# Mynd_TI_AMP.net
KiCad netlist of a schematic drawn in Altium Designer
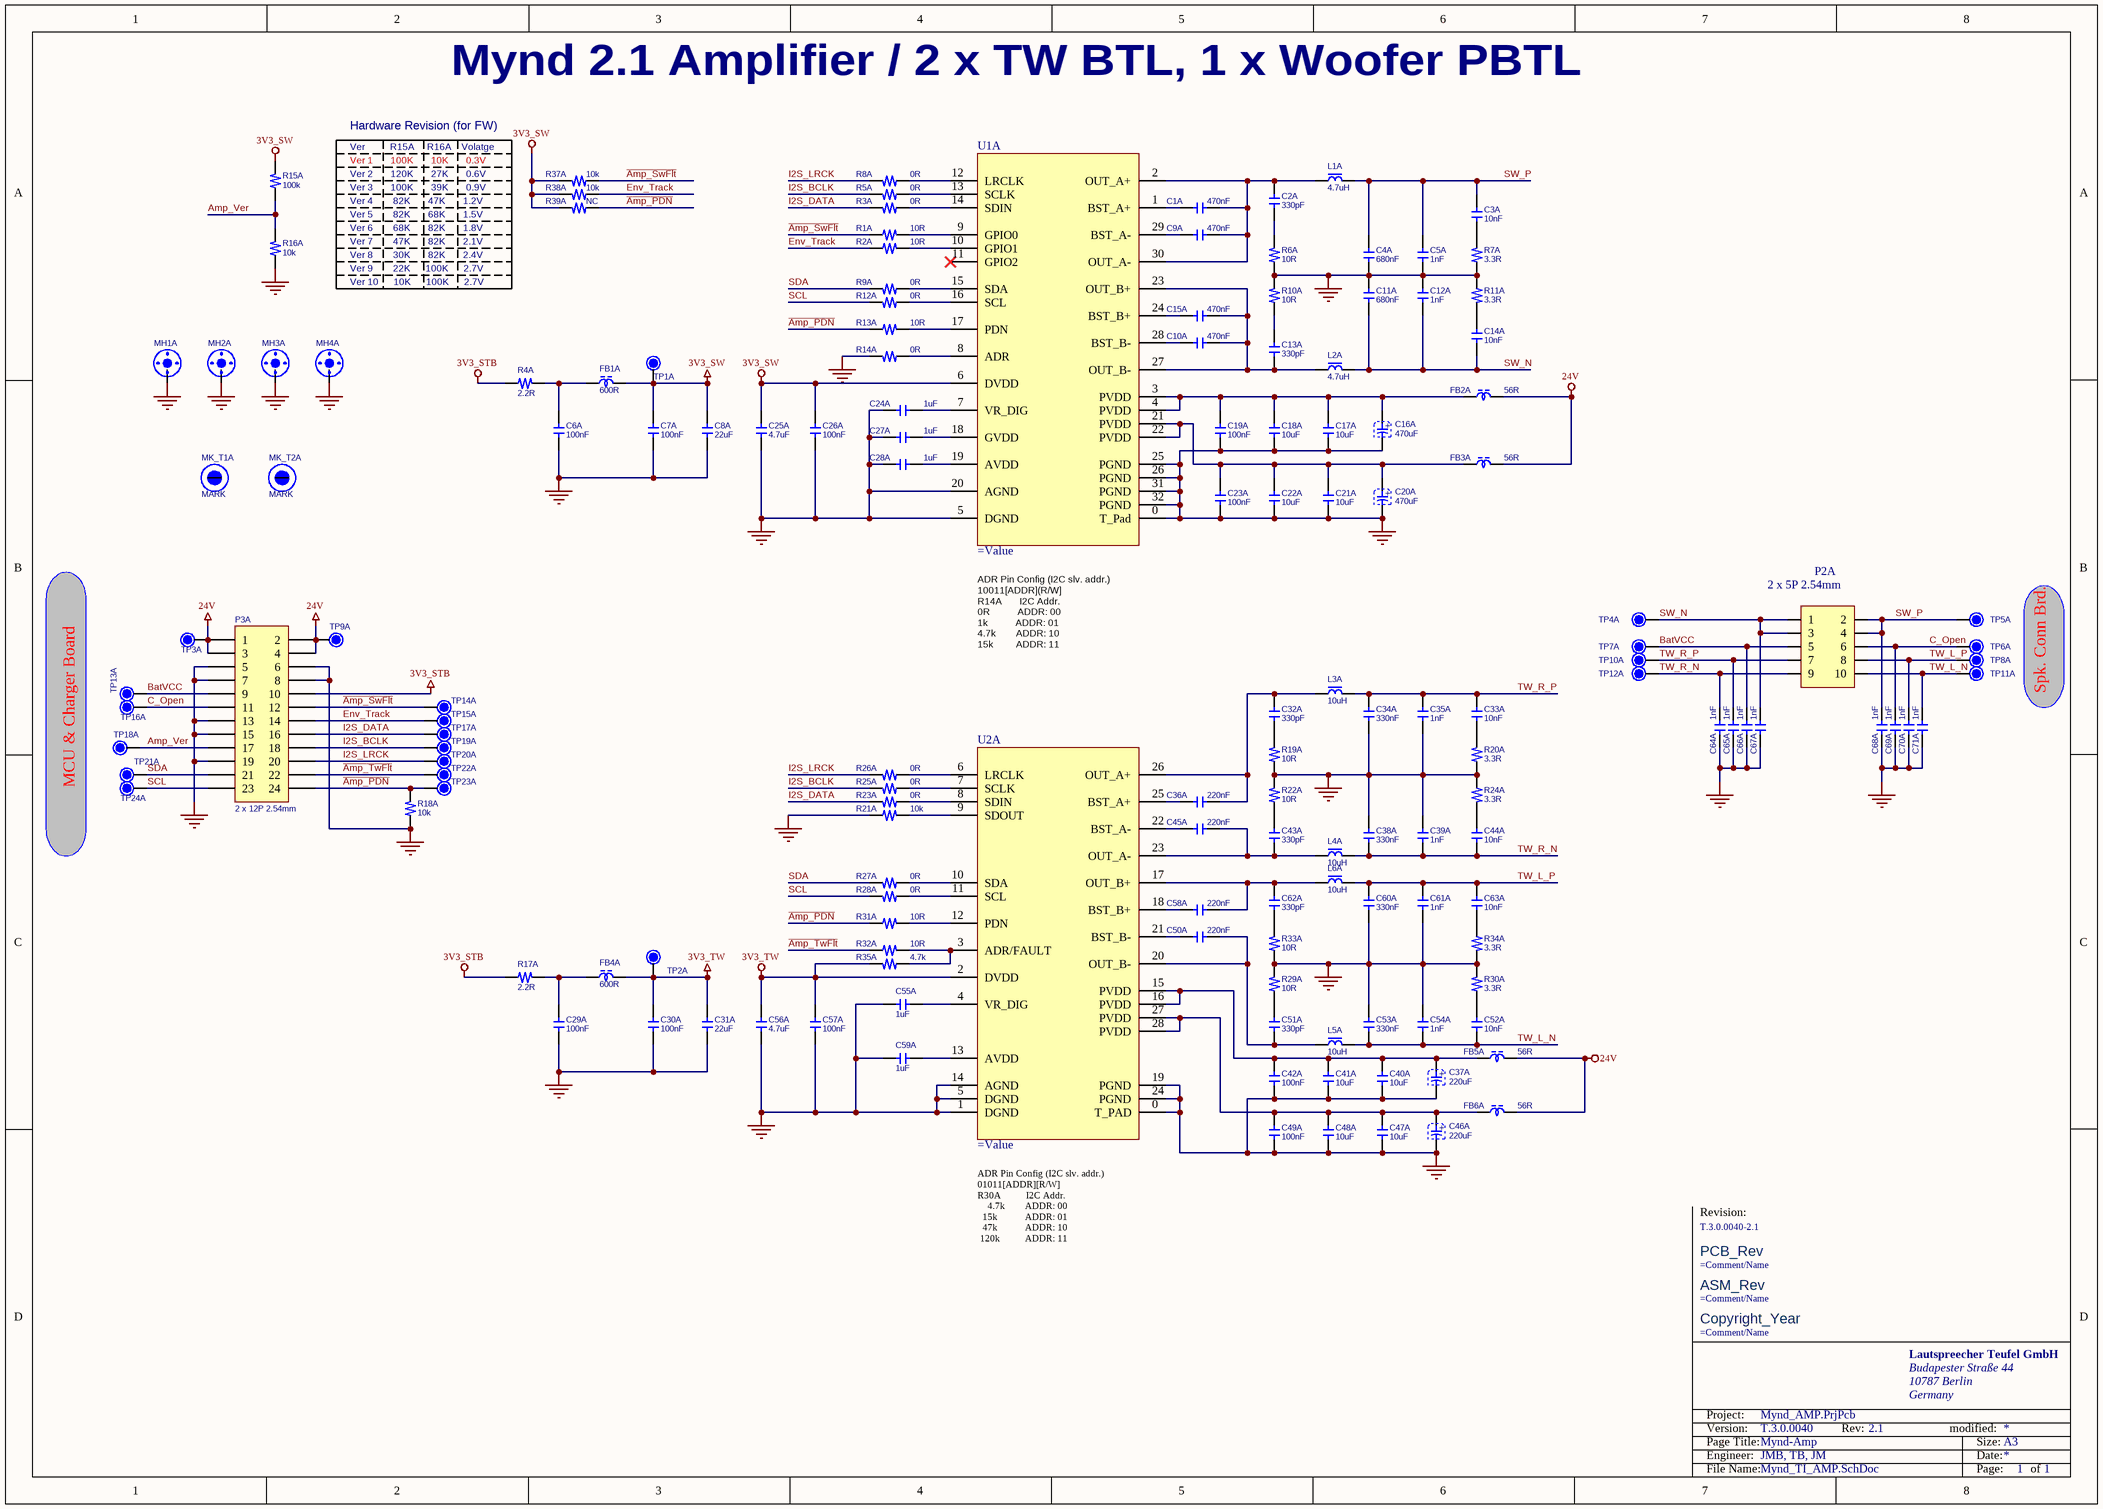
[diagram p0: Mynd_TI_AMP.SchDoc]

(export (version "E")
  (design (tool "Eeschema 10.0.6"))
  (components
    (comp (ref "C1A")
      (value "470nF")
      (footprint "C0603X100")
      (description "PSHF SMD M CAP 470nF 50V ±10% 0603 X7R")
      (fields (field (name "MANUFACTURER") "Multi-Sourced") (field (name "TOLERANCE") "±10%"))
      (libsource (lib "altium-import") (part "root_2_CAP1_"))
    )
    (comp (ref "C2A")
      (value "330pF")
      (footprint "C0603X80")
      (description "PSHF SMD M CAP 330pF 50V ±5% 0603 NPO")
      (fields (field (name "MANUFACTURER") "Multi-Sourced") (field (name "TOLERANCE") "±5%"))
      (libsource (lib "altium-import") (part "root_1_CAP1_"))
    )
    (comp (ref "C3A")
      (value "10nF")
      (footprint "C0603X100")
      (description "PSHF SMD M CAP 10nF 50V ±10% 0603 X7R")
      (fields (field (name "MANUFACTURER") "Multi-Sourced") (field (name "TOLERANCE") "±10%"))
      (libsource (lib "altium-import") (part "root_3_CAP1_"))
    )
    (comp (ref "C4A")
      (value "680nF")
      (footprint "C0805_125")
      (description "PSHF SMD M CAP 680nF 50V ±10% 0805 X7R")
      (fields (field (name "MANUFACTURER") "Multi-Sourced") (field (name "TOLERANCE") "±10%"))
      (libsource (lib "altium-import") (part "root_3_CAP1_"))
    )
    (comp (ref "C5A")
      (value "1nF")
      (footprint "C0805_125")
      (description "PSHF SMD M CAP 0.001uF 50V ±10% 0805 X7R")
      (fields (field (name "MANUFACTURER") "Multi-Sourced") (field (name "TOLERANCE") "±10%"))
      (libsource (lib "altium-import") (part "root_3_CAP1_"))
    )
    (comp (ref "C6A")
      (value "100nF")
      (footprint "C0603X105")
      (description "PSHF SMD M CAP 100nF 50V ±5% 0603 X7R")
      (fields (field (name "MANUFACTURER") "Multi-Sourced") (field (name "TOLERANCE") "±5%"))
      (libsource (lib "altium-import") (part "root_3_CAP1_"))
    )
    (comp (ref "C7A")
      (value "100nF")
      (footprint "C0603X105")
      (description "PSHF SMD M CAP 100nF 50V ±5% 0603 X7R")
      (fields (field (name "MANUFACTURER") "Multi-Sourced") (field (name "TOLERANCE") "±5%"))
      (libsource (lib "altium-import") (part "root_3_CAP1_"))
    )
    (comp (ref "C8A")
      (value "22uF")
      (footprint "C0805_145")
      (description "PSHF SMD M CAP 22uF 10V ±20% 0805 X5R")
      (fields (field (name "MANUFACTURER") "Multi-Sourced") (field (name "TOLERANCE") "±20%"))
      (libsource (lib "altium-import") (part "root_3_CAP1_"))
    )
    (comp (ref "C9A")
      (value "470nF")
      (footprint "C0603X100")
      (description "PSHF SMD M CAP 470nF 50V ±10% 0603 X7R")
      (fields (field (name "MANUFACTURER") "Multi-Sourced") (field (name "TOLERANCE") "±10%"))
      (libsource (lib "altium-import") (part "root_0_CAP1_"))
    )
    (comp (ref "C10A")
      (value "470nF")
      (footprint "C0603X100")
      (description "PSHF SMD M CAP 470nF 50V ±10% 0603 X7R")
      (fields (field (name "MANUFACTURER") "Multi-Sourced") (field (name "TOLERANCE") "±10%"))
      (libsource (lib "altium-import") (part "root_2_CAP1_"))
    )
    (comp (ref "C11A")
      (value "680nF")
      (footprint "C0805_125")
      (description "PSHF SMD M CAP 680nF 50V ±10% 0805 X7R")
      (fields (field (name "MANUFACTURER") "Multi-Sourced") (field (name "TOLERANCE") "±10%"))
      (libsource (lib "altium-import") (part "root_1_CAP1_"))
    )
    (comp (ref "C12A")
      (value "1nF")
      (footprint "C0805_125")
      (description "PSHF SMD M CAP 0.001uF 50V ±10% 0805 X7R")
      (fields (field (name "MANUFACTURER") "Multi-Sourced") (field (name "TOLERANCE") "±10%"))
      (libsource (lib "altium-import") (part "root_1_CAP1_"))
    )
    (comp (ref "C13A")
      (value "330pF")
      (footprint "C0603X80")
      (description "PSHF SMD M CAP 330pF 50V ±5% 0603 NPO")
      (fields (field (name "MANUFACTURER") "Multi-Sourced") (field (name "TOLERANCE") "±5%"))
      (libsource (lib "altium-import") (part "root_1_CAP1_"))
    )
    (comp (ref "C14A")
      (value "10nF")
      (footprint "C0603X100")
      (description "PSHF SMD M CAP 10nF 50V ±10% 0603 X7R")
      (fields (field (name "MANUFACTURER") "Multi-Sourced") (field (name "TOLERANCE") "±10%"))
      (libsource (lib "altium-import") (part "root_3_CAP1_"))
    )
    (comp (ref "C15A")
      (value "470nF")
      (footprint "C0603X100")
      (description "PSHF SMD M CAP 470nF 50V ±10% 0603 X7R")
      (fields (field (name "MANUFACTURER") "Multi-Sourced") (field (name "TOLERANCE") "±10%"))
      (libsource (lib "altium-import") (part "root_0_CAP1_"))
    )
    (comp (ref "C16A")
      (value "470uF")
      (footprint "ECAP_SMD_1000X1000")
      (description "PS SMD COND ELECT 470uF 35V ±20% 105℃")
      (fields (field (name "MANUFACTURER") "Multi-Sourced") (field (name "TOLERANCE") "±20%"))
      (libsource (lib "altium-import") (part "root_3_ECAP2_"))
    )
    (comp (ref "C17A")
      (value "10uF")
      (footprint "C1206")
      (description "PSHF SMD M CAP 10uF 50V ±10% 1206 X5R")
      (fields (field (name "MANUFACTURER") "Multi-Sourced") (field (name "TOLERANCE") "±10%"))
      (libsource (lib "altium-import") (part "root_3_CAP1_"))
    )
    (comp (ref "C18A")
      (value "10uF")
      (footprint "C1206")
      (description "PSHF SMD M CAP 10uF 50V ±10% 1206 X5R")
      (fields (field (name "MANUFACTURER") "Multi-Sourced") (field (name "TOLERANCE") "±10%"))
      (libsource (lib "altium-import") (part "root_3_CAP1_"))
    )
    (comp (ref "C19A")
      (value "100nF")
      (footprint "C0603X105")
      (description "PSHF SMD M CAP 100nF 50V ±5% 0603 X7R")
      (fields (field (name "MANUFACTURER") "Multi-Sourced") (field (name "TOLERANCE") "±5%"))
      (libsource (lib "altium-import") (part "root_3_CAP1_"))
    )
    (comp (ref "C20A")
      (value "470uF")
      (footprint "ECAP_SMD_1000X1000")
      (description "PS SMD COND ELECT 470uF 35V ±20% 105℃")
      (fields (field (name "MANUFACTURER") "Multi-Sourced") (field (name "TOLERANCE") "±20%"))
      (libsource (lib "altium-import") (part "root_3_ECAP2_"))
    )
    (comp (ref "C21A")
      (value "10uF")
      (footprint "C1206")
      (description "PSHF SMD M CAP 10uF 50V ±10% 1206 X5R")
      (fields (field (name "MANUFACTURER") "Multi-Sourced") (field (name "TOLERANCE") "±10%"))
      (libsource (lib "altium-import") (part "root_3_CAP1_"))
    )
    (comp (ref "C22A")
      (value "10uF")
      (footprint "C1206")
      (description "PSHF SMD M CAP 10uF 50V ±10% 1206 X5R")
      (fields (field (name "MANUFACTURER") "Multi-Sourced") (field (name "TOLERANCE") "±10%"))
      (libsource (lib "altium-import") (part "root_3_CAP1_"))
    )
    (comp (ref "C23A")
      (value "100nF")
      (footprint "C0603X105")
      (description "PSHF SMD M CAP 100nF 50V ±5% 0603 X7R")
      (fields (field (name "MANUFACTURER") "Multi-Sourced") (field (name "TOLERANCE") "±5%"))
      (libsource (lib "altium-import") (part "root_3_CAP1_"))
    )
    (comp (ref "C24A")
      (value "1uF")
      (footprint "C0603X105")
      (description "PSHF SMD M CAP 1uF 50V ±10% 0603 X7R")
      (fields (field (name "MANUFACTURER") "Multi-Sourced") (field (name "TOLERANCE") "±10%"))
      (libsource (lib "altium-import") (part "root_0_CAP1_"))
    )
    (comp (ref "C25A")
      (value "4.7uF")
      (footprint "C0805_145")
      (description "PSHF SMD M CAP 4.7uF 25V ±10% 0805 X7R")
      (fields (field (name "MANUFACTURER") "Multi-Sourced") (field (name "TOLERANCE") "±10%"))
      (libsource (lib "altium-import") (part "root_3_CAP1_"))
    )
    (comp (ref "C26A")
      (value "100nF")
      (footprint "C0603X105")
      (description "PSHF SMD M CAP 100nF 50V ±5% 0603 X7R")
      (fields (field (name "MANUFACTURER") "Multi-Sourced") (field (name "TOLERANCE") "±5%"))
      (libsource (lib "altium-import") (part "root_3_CAP1_"))
    )
    (comp (ref "C27A")
      (value "1uF")
      (footprint "C0603X105")
      (description "PSHF SMD M CAP 1uF 50V ±10% 0603 X7R")
      (fields (field (name "MANUFACTURER") "Multi-Sourced") (field (name "TOLERANCE") "±10%"))
      (libsource (lib "altium-import") (part "root_0_CAP1_"))
    )
    (comp (ref "C28A")
      (value "1uF")
      (footprint "C0603X105")
      (description "PSHF SMD M CAP 1uF 50V ±10% 0603 X7R")
      (fields (field (name "MANUFACTURER") "Multi-Sourced") (field (name "TOLERANCE") "±10%"))
      (libsource (lib "altium-import") (part "root_0_CAP1_"))
    )
    (comp (ref "C29A")
      (value "100nF")
      (footprint "C0603X105")
      (description "PSHF SMD M CAP 100nF 50V ±5% 0603 X7R")
      (fields (field (name "MANUFACTURER") "Multi-Sourced") (field (name "TOLERANCE") "±5%"))
      (libsource (lib "altium-import") (part "root_3_CAP1_"))
    )
    (comp (ref "C30A")
      (value "100nF")
      (footprint "C0603X105")
      (description "PSHF SMD M CAP 100nF 50V ±5% 0603 X7R")
      (fields (field (name "MANUFACTURER") "Multi-Sourced") (field (name "TOLERANCE") "±5%"))
      (libsource (lib "altium-import") (part "root_3_CAP1_"))
    )
    (comp (ref "C31A")
      (value "22uF")
      (footprint "C0805_145")
      (description "PSHF SMD M CAP 22uF 10V ±20% 0805 X5R")
      (fields (field (name "MANUFACTURER") "Multi-Sourced") (field (name "TOLERANCE") "±20%"))
      (libsource (lib "altium-import") (part "root_3_CAP1_"))
    )
    (comp (ref "C32A")
      (value "330pF")
      (footprint "C0603X80")
      (description "PSHF SMD M CAP 330pF 50V ±5% 0603 NPO")
      (fields (field (name "MANUFACTURER") "Multi-Sourced") (field (name "TOLERANCE") "±5%"))
      (libsource (lib "altium-import") (part "root_1_CAP1_"))
    )
    (comp (ref "C33A")
      (value "10nF")
      (footprint "C0603X100")
      (description "PSHF SMD M CAP 10nF 50V ±10% 0603 X7R")
      (fields (field (name "MANUFACTURER") "Multi-Sourced") (field (name "TOLERANCE") "±10%"))
      (libsource (lib "altium-import") (part "root_3_CAP1_"))
    )
    (comp (ref "C34A")
      (value "330nF")
      (footprint "C0805_125")
      (description "PSHF SMD M CAP 330nF 50V ±10% 0805 X7R")
      (fields (field (name "MANUFACTURER") "Multi-Sourced") (field (name "TOLERANCE") "±10%"))
      (libsource (lib "altium-import") (part "root_3_CAP1_"))
    )
    (comp (ref "C35A")
      (value "1nF")
      (footprint "C0805_125")
      (description "PSHF SMD M CAP 0.001uF 50V ±10% 0805 X7R")
      (fields (field (name "MANUFACTURER") "Multi-Sourced") (field (name "TOLERANCE") "±10%"))
      (libsource (lib "altium-import") (part "root_3_CAP1_"))
    )
    (comp (ref "C36A")
      (value "220nF")
      (footprint "C0603X100")
      (description "PSHF SMD M CAP 220nF 50V ±10% 0603 X7R")
      (fields (field (name "MANUFACTURER") "Multi-Sourced") (field (name "TOLERANCE") "±10%"))
      (libsource (lib "altium-import") (part "root_2_CAP1_"))
    )
    (comp (ref "C37A")
      (value "220uF")
      (footprint "ECAP_SMD_800X1000")
      (description "PS SMD COND ELECT 220uF 35V ±20% 105℃")
      (fields (field (name "MANUFACTURER") "[LELON]") (field (name "TOLERANCE") "±20%"))
      (libsource (lib "altium-import") (part "root_3_ECAP2_"))
    )
    (comp (ref "C38A")
      (value "330nF")
      (footprint "C0805_125")
      (description "PSHF SMD M CAP 330nF 50V ±10% 0805 X7R")
      (fields (field (name "MANUFACTURER") "Multi-Sourced") (field (name "TOLERANCE") "±10%"))
      (libsource (lib "altium-import") (part "root_1_CAP1_"))
    )
    (comp (ref "C39A")
      (value "1nF")
      (footprint "C0805_125")
      (description "PSHF SMD M CAP 0.001uF 50V ±10% 0805 X7R")
      (fields (field (name "MANUFACTURER") "Multi-Sourced") (field (name "TOLERANCE") "±10%"))
      (libsource (lib "altium-import") (part "root_1_CAP1_"))
    )
    (comp (ref "C40A")
      (value "10uF")
      (footprint "C1206")
      (description "PSHF SMD M CAP 10uF 50V ±10% 1206 X5R")
      (fields (field (name "MANUFACTURER") "Multi-Sourced") (field (name "TOLERANCE") "±10%"))
      (libsource (lib "altium-import") (part "root_3_CAP1_"))
    )
    (comp (ref "C41A")
      (value "10uF")
      (footprint "C1206")
      (description "PSHF SMD M CAP 10uF 50V ±10% 1206 X5R")
      (fields (field (name "MANUFACTURER") "Multi-Sourced") (field (name "TOLERANCE") "±10%"))
      (libsource (lib "altium-import") (part "root_3_CAP1_"))
    )
    (comp (ref "C42A")
      (value "100nF")
      (footprint "C0603X105")
      (description "PSHF SMD M CAP 100nF 50V ±5% 0603 X7R")
      (fields (field (name "MANUFACTURER") "Multi-Sourced") (field (name "TOLERANCE") "±5%"))
      (libsource (lib "altium-import") (part "root_3_CAP1_"))
    )
    (comp (ref "C43A")
      (value "330pF")
      (footprint "C0603X80")
      (description "PSHF SMD M CAP 330pF 50V ±5% 0603 NPO")
      (fields (field (name "MANUFACTURER") "Multi-Sourced") (field (name "TOLERANCE") "±5%"))
      (libsource (lib "altium-import") (part "root_1_CAP1_"))
    )
    (comp (ref "C44A")
      (value "10nF")
      (footprint "C0603X100")
      (description "PSHF SMD M CAP 10nF 50V ±10% 0603 X7R")
      (fields (field (name "MANUFACTURER") "Multi-Sourced") (field (name "TOLERANCE") "±10%"))
      (libsource (lib "altium-import") (part "root_3_CAP1_"))
    )
    (comp (ref "C45A")
      (value "220nF")
      (footprint "C0603X100")
      (description "PSHF SMD M CAP 220nF 50V ±10% 0603 X7R")
      (fields (field (name "MANUFACTURER") "Multi-Sourced") (field (name "TOLERANCE") "±10%"))
      (libsource (lib "altium-import") (part "root_0_CAP1_"))
    )
    (comp (ref "C46A")
      (value "220uF")
      (footprint "ECAP_SMD_800X1000")
      (description "PS SMD COND ELECT 220uF 35V ±20% 105℃")
      (fields (field (name "MANUFACTURER") "[LELON]") (field (name "TOLERANCE") "±20%"))
      (libsource (lib "altium-import") (part "root_3_ECAP2_"))
    )
    (comp (ref "C47A")
      (value "10uF")
      (footprint "C1206")
      (description "PSHF SMD M CAP 10uF 50V ±10% 1206 X5R")
      (fields (field (name "MANUFACTURER") "Multi-Sourced") (field (name "TOLERANCE") "±10%"))
      (libsource (lib "altium-import") (part "root_3_CAP1_"))
    )
    (comp (ref "C48A")
      (value "10uF")
      (footprint "C1206")
      (description "PSHF SMD M CAP 10uF 50V ±10% 1206 X5R")
      (fields (field (name "MANUFACTURER") "Multi-Sourced") (field (name "TOLERANCE") "±10%"))
      (libsource (lib "altium-import") (part "root_3_CAP1_"))
    )
    (comp (ref "C49A")
      (value "100nF")
      (footprint "C0603X105")
      (description "PSHF SMD M CAP 100nF 50V ±5% 0603 X7R")
      (fields (field (name "MANUFACTURER") "Multi-Sourced") (field (name "TOLERANCE") "±5%"))
      (libsource (lib "altium-import") (part "root_3_CAP1_"))
    )
    (comp (ref "C50A")
      (value "220nF")
      (footprint "C0603X100")
      (description "PSHF SMD M CAP 220nF 50V ±10% 0603 X7R")
      (fields (field (name "MANUFACTURER") "Multi-Sourced") (field (name "TOLERANCE") "±10%"))
      (libsource (lib "altium-import") (part "root_0_mirrored_CAP1_"))
    )
    (comp (ref "C51A")
      (value "330pF")
      (footprint "C0603X80")
      (description "PSHF SMD M CAP 330pF 50V ±5% 0603 NPO")
      (fields (field (name "MANUFACTURER") "Multi-Sourced") (field (name "TOLERANCE") "±5%"))
      (libsource (lib "altium-import") (part "root_3_mirrored_CAP1_"))
    )
    (comp (ref "C52A")
      (value "10nF")
      (footprint "C0603X100")
      (description "PSHF SMD M CAP 10nF 50V ±10% 0603 X7R")
      (fields (field (name "MANUFACTURER") "Multi-Sourced") (field (name "TOLERANCE") "±10%"))
      (libsource (lib "altium-import") (part "root_1_mirrored_CAP1_"))
    )
    (comp (ref "C53A")
      (value "330nF")
      (footprint "C0805_125")
      (description "PSHF SMD M CAP 330nF 50V ±10% 0805 X7R")
      (fields (field (name "MANUFACTURER") "Multi-Sourced") (field (name "TOLERANCE") "±10%"))
      (libsource (lib "altium-import") (part "root_1_mirrored_CAP1_"))
    )
    (comp (ref "C54A")
      (value "1nF")
      (footprint "C0805_125")
      (description "PSHF SMD M CAP 0.001uF 50V ±10% 0805 X7R")
      (fields (field (name "MANUFACTURER") "Multi-Sourced") (field (name "TOLERANCE") "±10%"))
      (libsource (lib "altium-import") (part "root_1_mirrored_CAP1_"))
    )
    (comp (ref "C55A")
      (value "1uF")
      (footprint "C0603X105")
      (description "PSHF SMD M CAP 1uF 50V ±10% 0603 X7R")
      (fields (field (name "MANUFACTURER") "Multi-Sourced") (field (name "TOLERANCE") "±10%"))
      (libsource (lib "altium-import") (part "root_0_CAP1_"))
    )
    (comp (ref "C56A")
      (value "4.7uF")
      (footprint "C0805_145")
      (description "PSHF SMD M CAP 4.7uF 25V ±10% 0805 X7R")
      (fields (field (name "MANUFACTURER") "Multi-Sourced") (field (name "TOLERANCE") "±10%"))
      (libsource (lib "altium-import") (part "root_3_CAP1_"))
    )
    (comp (ref "C57A")
      (value "100nF")
      (footprint "C0603X105")
      (description "PSHF SMD M CAP 100nF 50V ±5% 0603 X7R")
      (fields (field (name "MANUFACTURER") "Multi-Sourced") (field (name "TOLERANCE") "±5%"))
      (libsource (lib "altium-import") (part "root_3_CAP1_"))
    )
    (comp (ref "C58A")
      (value "220nF")
      (footprint "C0603X100")
      (description "PSHF SMD M CAP 220nF 50V ±10% 0603 X7R")
      (fields (field (name "MANUFACTURER") "Multi-Sourced") (field (name "TOLERANCE") "±10%"))
      (libsource (lib "altium-import") (part "root_2_mirrored_CAP1_"))
    )
    (comp (ref "C59A")
      (value "1uF")
      (footprint "C0603X105")
      (description "PSHF SMD M CAP 1uF 50V ±10% 0603 X7R")
      (fields (field (name "MANUFACTURER") "Multi-Sourced") (field (name "TOLERANCE") "±10%"))
      (libsource (lib "altium-import") (part "root_0_CAP1_"))
    )
    (comp (ref "C60A")
      (value "330nF")
      (footprint "C0805_125")
      (description "PSHF SMD M CAP 330nF 50V ±10% 0805 X7R")
      (fields (field (name "MANUFACTURER") "Multi-Sourced") (field (name "TOLERANCE") "±10%"))
      (libsource (lib "altium-import") (part "root_3_mirrored_CAP1_"))
    )
    (comp (ref "C61A")
      (value "1nF")
      (footprint "C0805_125")
      (description "PSHF SMD M CAP 0.001uF 50V ±10% 0805 X7R")
      (fields (field (name "MANUFACTURER") "Multi-Sourced") (field (name "TOLERANCE") "±10%"))
      (libsource (lib "altium-import") (part "root_3_mirrored_CAP1_"))
    )
    (comp (ref "C62A")
      (value "330pF")
      (footprint "C0603X80")
      (description "PSHF SMD M CAP 330pF 50V ±5% 0603 NPO")
      (fields (field (name "MANUFACTURER") "Multi-Sourced") (field (name "TOLERANCE") "±5%"))
      (libsource (lib "altium-import") (part "root_3_mirrored_CAP1_"))
    )
    (comp (ref "C63A")
      (value "10nF")
      (footprint "C0603X100")
      (description "PSHF SMD M CAP 10nF 50V ±10% 0603 X7R")
      (fields (field (name "MANUFACTURER") "Multi-Sourced") (field (name "TOLERANCE") "±10%"))
      (libsource (lib "altium-import") (part "root_1_mirrored_CAP1_"))
    )
    (comp (ref "C64A")
      (value "1nF")
      (footprint "C0805_125")
      (description "PSHF SMD M CAP 0.001uF 50V ±10% 0805 X7R")
      (fields (field (name "MANUFACTURER") "Multi-Sourced") (field (name "TOLERANCE") "±10%"))
      (libsource (lib "altium-import") (part "root_3_CAP1_"))
    )
    (comp (ref "C65A")
      (value "1nF")
      (footprint "C0805_125")
      (description "PSHF SMD M CAP 0.001uF 50V ±10% 0805 X7R")
      (fields (field (name "MANUFACTURER") "Multi-Sourced") (field (name "TOLERANCE") "±10%"))
      (libsource (lib "altium-import") (part "root_3_CAP1_"))
    )
    (comp (ref "C66A")
      (value "1nF")
      (footprint "C0805_125")
      (description "PSHF SMD M CAP 0.001uF 50V ±10% 0805 X7R")
      (fields (field (name "MANUFACTURER") "Multi-Sourced") (field (name "TOLERANCE") "±10%"))
      (libsource (lib "altium-import") (part "root_3_CAP1_"))
    )
    (comp (ref "C67A")
      (value "1nF")
      (footprint "C0805_125")
      (description "PSHF SMD M CAP 0.001uF 50V ±10% 0805 X7R")
      (fields (field (name "MANUFACTURER") "Multi-Sourced") (field (name "TOLERANCE") "±10%"))
      (libsource (lib "altium-import") (part "root_3_CAP1_"))
    )
    (comp (ref "C68A")
      (value "1nF")
      (footprint "C0805_125")
      (description "PSHF SMD M CAP 0.001uF 50V ±10% 0805 X7R")
      (fields (field (name "MANUFACTURER") "Multi-Sourced") (field (name "TOLERANCE") "±10%"))
      (libsource (lib "altium-import") (part "root_3_CAP1_"))
    )
    (comp (ref "C69A")
      (value "1nF")
      (footprint "C0805_125")
      (description "PSHF SMD M CAP 0.001uF 50V ±10% 0805 X7R")
      (fields (field (name "MANUFACTURER") "Multi-Sourced") (field (name "TOLERANCE") "±10%"))
      (libsource (lib "altium-import") (part "root_3_CAP1_"))
    )
    (comp (ref "C70A")
      (value "1nF")
      (footprint "C0805_125")
      (description "PSHF SMD M CAP 0.001uF 50V ±10% 0805 X7R")
      (fields (field (name "MANUFACTURER") "Multi-Sourced") (field (name "TOLERANCE") "±10%"))
      (libsource (lib "altium-import") (part "root_3_CAP1_"))
    )
    (comp (ref "C71A")
      (value "1nF")
      (footprint "C0805_125")
      (description "PSHF SMD M CAP 0.001uF 50V ±10% 0805 X7R")
      (fields (field (name "MANUFACTURER") "Multi-Sourced") (field (name "TOLERANCE") "±10%"))
      (libsource (lib "altium-import") (part "root_3_CAP1_"))
    )
    (comp (ref "FB1A")
      (value "600R")
      (footprint "L0603")
      (description "PSHF SMD FERRITE BEAD 600OHM 25% 0603")
      (fields (field (name "MANUFACTURER") "TSA") (field (name "TOLERANCE") "1:25%"))
      (libsource (lib "altium-import") (part "root_0_Bead1_"))
    )
    (comp (ref "FB2A")
      (value "56R")
      (footprint "L1612")
      (description "SMD FERRITE BEAD 56Ohm 25% 1612")
      (fields (field (name "MANUFACTURER") "TSA") (field (name "TOLERANCE") "1:25%"))
      (libsource (lib "altium-import") (part "root_0_mirrored_Bead1_"))
    )
    (comp (ref "FB3A")
      (value "56R")
      (footprint "L1612")
      (description "SMD FERRITE BEAD 56Ohm 25% 1612")
      (fields (field (name "MANUFACTURER") "TSA") (field (name "TOLERANCE") "1:25%"))
      (libsource (lib "altium-import") (part "root_0_mirrored_Bead1_"))
    )
    (comp (ref "FB4A")
      (value "600R")
      (footprint "L0603")
      (description "PSHF SMD FERRITE BEAD 600OHM 25% 0603")
      (fields (field (name "MANUFACTURER") "TSA") (field (name "TOLERANCE") "1:25%"))
      (libsource (lib "altium-import") (part "root_0_Bead1_"))
    )
    (comp (ref "FB5A")
      (value "56R")
      (footprint "L1612")
      (description "SMD FERRITE BEAD 56Ohm 25% 1612")
      (fields (field (name "MANUFACTURER") "TSA") (field (name "TOLERANCE") "1:25%"))
      (libsource (lib "altium-import") (part "root_0_mirrored_Bead1_"))
    )
    (comp (ref "FB6A")
      (value "56R")
      (footprint "L1612")
      (description "SMD FERRITE BEAD 56Ohm 25% 1612")
      (fields (field (name "MANUFACTURER") "TSA") (field (name "TOLERANCE") "1:25%"))
      (libsource (lib "altium-import") (part "root_0_Bead1_"))
    )
    (comp (ref "L1A")
      (value "4.7uH")
      (footprint "IND_SMD_YT_SQU_L78XW70XH50")
      (description "PS INDUCTOR 4.7uH 20% 6.5A 7.8x7x4.8")
      (fields (field (name "MANUFACTURER") "CHAMPIONS") (field (name "VOLTAGE") "1V"))
      (libsource (lib "altium-import") (part "root_0_INDUCTOR1_"))
    )
    (comp (ref "L2A")
      (value "4.7uH")
      (footprint "IND_SMD_YT_SQU_L78XW70XH50")
      (description "PS INDUCTOR 4.7uH 20% 6.5A 7.8x7x4.8")
      (fields (field (name "MANUFACTURER") "CHAMPIONS") (field (name "VOLTAGE") "1V"))
      (libsource (lib "altium-import") (part "root_0_INDUCTOR1_"))
    )
    (comp (ref "L3A")
      (value "10uH")
      (footprint "IND_SMD_YT_SQU_L78XW70XH30")
      (description "GP SMD INDUCTOR 10uH 1MHz 1V NORM")
      (fields (field (name "MANUFACTURER") "[CHAMPIONS]") (field (name "VOLTAGE") "1V"))
      (libsource (lib "altium-import") (part "root_0_INDUCTOR1_"))
    )
    (comp (ref "L4A")
      (value "10uH")
      (footprint "IND_SMD_YT_SQU_L78XW70XH30")
      (description "GP SMD INDUCTOR 10uH 1MHz 1V NORM")
      (fields (field (name "MANUFACTURER") "[CHAMPIONS]") (field (name "VOLTAGE") "1V"))
      (libsource (lib "altium-import") (part "root_0_INDUCTOR1_"))
    )
    (comp (ref "L5A")
      (value "10uH")
      (footprint "IND_SMD_YT_SQU_L78XW70XH30")
      (description "GP SMD INDUCTOR 10uH 1MHz 1V NORM")
      (fields (field (name "MANUFACTURER") "[CHAMPIONS]") (field (name "VOLTAGE") "1V"))
      (libsource (lib "altium-import") (part "root_0_INDUCTOR1_"))
    )
    (comp (ref "L6A")
      (value "10uH")
      (footprint "IND_SMD_YT_SQU_L78XW70XH30")
      (description "GP SMD INDUCTOR 10uH 1MHz 1V NORM")
      (fields (field (name "MANUFACTURER") "[CHAMPIONS]") (field (name "VOLTAGE") "1V"))
      (libsource (lib "altium-import") (part "root_0_INDUCTOR1_"))
    )
    (comp (ref "MH1A")
      (value "SCREW_HOLE_D32")
      (footprint "SCREW_D32")
      (description "SCREW_HOLE D3.2mm")
      (libsource (lib "altium-import") (part "root_1_SCREW_HOLE_"))
    )
    (comp (ref "MH2A")
      (value "SCREW_HOLE_D32")
      (footprint "SCREW_D32")
      (description "SCREW_HOLE D3.2mm")
      (libsource (lib "altium-import") (part "root_1_SCREW_HOLE_"))
    )
    (comp (ref "MH3A")
      (value "SCREW_HOLE_D32")
      (footprint "SCREW_D32")
      (description "SCREW_HOLE D3.2mm")
      (libsource (lib "altium-import") (part "root_1_SCREW_HOLE_"))
    )
    (comp (ref "MH4A")
      (value "SCREW_HOLE_D32")
      (footprint "SCREW_D32")
      (description "SCREW_HOLE D3.2mm")
      (libsource (lib "altium-import") (part "root_1_SCREW_HOLE_"))
    )
    (comp (ref "MK_T1A")
      (value "MARK")
      (footprint "MARK")
      (description "MARK DOT")
      (libsource (lib "altium-import") (part "root_0_MARK_"))
    )
    (comp (ref "MK_T2A")
      (value "MARK")
      (footprint "MARK")
      (description "MARK DOT")
      (libsource (lib "altium-import") (part "root_0_MARK_"))
    )
    (comp (ref "P2A")
      (value "2 x 5P 2.54mm")
      (footprint "female_2X5_254")
      (description "SMD BTB CONNECTOR 10P P2.54mm GOLD")
      (fields (field (name "MANUFACTURER") "MINGHENG"))
      (libsource (lib "altium-import") (part "root_0_CON 2X5P_"))
    )
    (comp (ref "P3A")
      (value "2 x 12P 2.54mm")
      (footprint "Pin_Header_SMD_2X12_254")
      (description "SMD BTB CONNECTOR 24P P2.54mm GOLD")
      (fields (field (name "MANUFACTURER") "MINGHENG"))
      (libsource (lib "altium-import") (part "root_0_CON 2x12P_"))
    )
    (comp (ref "R1A")
      (value "10R")
      (footprint "R0603")
      (description "PS SMD RES. 10OHM 1/10W 5% 0603")
      (fields (field (name "TOLERANCE") "1%") (field (name "MANUFACTURER") "Multi-Sourced"))
      (libsource (lib "altium-import") (part "root_2_RES1_"))
    )
    (comp (ref "R2A")
      (value "10R")
      (footprint "R0603")
      (description "PS SMD RES. 10OHM 1/10W 5% 0603")
      (fields (field (name "TOLERANCE") "1%") (field (name "MANUFACTURER") "Multi-Sourced"))
      (libsource (lib "altium-import") (part "root_2_RES1_"))
    )
    (comp (ref "R3A")
      (value "0R")
      (footprint "R0603")
      (description "PS SMD RES. 0OHM 1/10W 5% 0603")
      (fields (field (name "TOLERANCE") "1%") (field (name "MANUFACTURER") "Multi-Sourced"))
      (libsource (lib "altium-import") (part "root_0_RES1_"))
    )
    (comp (ref "R4A")
      (value "2.2R")
      (footprint "R0603")
      (description "PS SMD RES. 2.2OHM 1/10W 5% 0603")
      (fields (field (name "TOLERANCE") "1%") (field (name "MANUFACTURER") "Multi-Sourced"))
      (libsource (lib "altium-import") (part "root_2_RES1_"))
    )
    (comp (ref "R5A")
      (value "0R")
      (footprint "R0603")
      (description "PS SMD RES. 0OHM 1/10W 5% 0603")
      (fields (field (name "TOLERANCE") "1%") (field (name "MANUFACTURER") "Multi-Sourced"))
      (libsource (lib "altium-import") (part "root_0_RES1_"))
    )
    (comp (ref "R6A")
      (value "10R")
      (footprint "R1206")
      (description "PS SMD RES. 10OHM 1/4W 5% 1206")
      (fields (field (name "TOLERANCE") "1%") (field (name "MANUFACTURER") "Multi-Sourced"))
      (libsource (lib "altium-import") (part "root_3_RES1_"))
    )
    (comp (ref "R7A")
      (value "3.3R")
      (footprint "R0603")
      (description "PS SMD RES. 3.3OHM 1/10W 1% 0603")
      (fields (field (name "TOLERANCE") "1%") (field (name "MANUFACTURER") "Multi-Sourced"))
      (libsource (lib "altium-import") (part "root_3_RES1_"))
    )
    (comp (ref "R8A")
      (value "0R")
      (footprint "R0603")
      (description "PS SMD RES. 0OHM 1/10W 5% 0603")
      (fields (field (name "TOLERANCE") "1%") (field (name "MANUFACTURER") "Multi-Sourced"))
      (libsource (lib "altium-import") (part "root_0_RES1_"))
    )
    (comp (ref "R9A")
      (value "0R")
      (footprint "R0603")
      (description "PS SMD RES. 0OHM 1/10W 5% 0603")
      (fields (field (name "TOLERANCE") "1%") (field (name "MANUFACTURER") "Multi-Sourced"))
      (libsource (lib "altium-import") (part "root_0_RES1_"))
    )
    (comp (ref "R10A")
      (value "10R")
      (footprint "R1206")
      (description "PS SMD RES. 10OHM 1/4W 5% 1206")
      (fields (field (name "TOLERANCE") "1%") (field (name "MANUFACTURER") "Multi-Sourced"))
      (libsource (lib "altium-import") (part "root_3_RES1_"))
    )
    (comp (ref "R11A")
      (value "3.3R")
      (footprint "R0603")
      (description "PS SMD RES. 3.3OHM 1/10W 1% 0603")
      (fields (field (name "TOLERANCE") "1%") (field (name "MANUFACTURER") "Multi-Sourced"))
      (libsource (lib "altium-import") (part "root_1_RES1_"))
    )
    (comp (ref "R12A")
      (value "0R")
      (footprint "R0603")
      (description "PS SMD RES. 0OHM 1/10W 5% 0603")
      (fields (field (name "TOLERANCE") "1%") (field (name "MANUFACTURER") "Multi-Sourced"))
      (libsource (lib "altium-import") (part "root_0_RES1_"))
    )
    (comp (ref "R13A")
      (value "10R")
      (footprint "R0603")
      (description "PS SMD RES. 10OHM 1/10W 5% 0603")
      (fields (field (name "TOLERANCE") "1%") (field (name "MANUFACTURER") "Multi-Sourced"))
      (libsource (lib "altium-import") (part "root_2_RES1_"))
    )
    (comp (ref "R14A")
      (value "0R")
      (footprint "R0603")
      (description "PS SMD RES. 0OHM 1/10W 5% 0603")
      (fields (field (name "TOLERANCE") "1%") (field (name "MANUFACTURER") "Multi-Sourced"))
      (libsource (lib "altium-import") (part "root_0_RES1_"))
    )
    (comp (ref "R15A")
      (value "100k")
      (footprint "R0603")
      (description "PS SMD RES. 100KOHM 1/10W 1% 0603")
      (fields (field (name "TOLERANCE") "1%") (field (name "MANUFACTURER") "Multi-Sourced"))
      (libsource (lib "altium-import") (part "root_3_RES1_"))
    )
    (comp (ref "R16A")
      (value "10k")
      (footprint "R0603")
      (description "PS SMD RES. 10KOHM 1/10W 1% 0603")
      (fields (field (name "TOLERANCE") "1%") (field (name "MANUFACTURER") "Multi-Sourced"))
      (libsource (lib "altium-import") (part "root_3_RES1_"))
    )
    (comp (ref "R17A")
      (value "2.2R")
      (footprint "R0603")
      (description "PS SMD RES. 2.2OHM 1/10W 5% 0603")
      (fields (field (name "TOLERANCE") "1%") (field (name "MANUFACTURER") "Multi-Sourced"))
      (libsource (lib "altium-import") (part "root_2_RES1_"))
    )
    (comp (ref "R18A")
      (value "10k")
      (footprint "R0603")
      (description "PS SMD RES. 10KOHM 1/10W 1% 0603")
      (fields (field (name "TOLERANCE") "1%") (field (name "MANUFACTURER") "Multi-Sourced"))
      (libsource (lib "altium-import") (part "root_3_RES1_"))
    )
    (comp (ref "R19A")
      (value "10R")
      (footprint "R1206")
      (description "PS SMD RES. 10OHM 1/4W 5% 1206")
      (fields (field (name "TOLERANCE") "1%") (field (name "MANUFACTURER") "Multi-Sourced"))
      (libsource (lib "altium-import") (part "root_3_RES1_"))
    )
    (comp (ref "R20A")
      (value "3.3R")
      (footprint "R0603")
      (description "PS SMD RES. 3.3OHM 1/10W 1% 0603")
      (fields (field (name "TOLERANCE") "1%") (field (name "MANUFACTURER") "Multi-Sourced"))
      (libsource (lib "altium-import") (part "root_3_RES1_"))
    )
    (comp (ref "R21A")
      (value "10k")
      (footprint "R0603")
      (description "PS SMD RES. 10KOHM 1/10W 1% 0603")
      (fields (field (name "TOLERANCE") "1%") (field (name "MANUFACTURER") "Multi-Sourced"))
      (libsource (lib "altium-import") (part "root_2_RES1_"))
    )
    (comp (ref "R22A")
      (value "10R")
      (footprint "R1206")
      (description "PS SMD RES. 10OHM 1/4W 5% 1206")
      (fields (field (name "TOLERANCE") "1%") (field (name "MANUFACTURER") "Multi-Sourced"))
      (libsource (lib "altium-import") (part "root_3_RES1_"))
    )
    (comp (ref "R23A")
      (value "0R")
      (footprint "R0603")
      (description "PS SMD RES. 0OHM 1/10W 5% 0603")
      (fields (field (name "TOLERANCE") "1%") (field (name "MANUFACTURER") "Multi-Sourced"))
      (libsource (lib "altium-import") (part "root_0_RES1_"))
    )
    (comp (ref "R24A")
      (value "3.3R")
      (footprint "R0603")
      (description "PS SMD RES. 3.3OHM 1/10W 1% 0603")
      (fields (field (name "TOLERANCE") "1%") (field (name "MANUFACTURER") "Multi-Sourced"))
      (libsource (lib "altium-import") (part "root_1_RES1_"))
    )
    (comp (ref "R25A")
      (value "0R")
      (footprint "R0603")
      (description "PS SMD RES. 0OHM 1/10W 5% 0603")
      (fields (field (name "TOLERANCE") "1%") (field (name "MANUFACTURER") "Multi-Sourced"))
      (libsource (lib "altium-import") (part "root_0_RES1_"))
    )
    (comp (ref "R26A")
      (value "0R")
      (footprint "R0603")
      (description "PS SMD RES. 0OHM 1/10W 5% 0603")
      (fields (field (name "TOLERANCE") "1%") (field (name "MANUFACTURER") "Multi-Sourced"))
      (libsource (lib "altium-import") (part "root_0_RES1_"))
    )
    (comp (ref "R27A")
      (value "0R")
      (footprint "R0603")
      (description "PS SMD RES. 0OHM 1/10W 5% 0603")
      (fields (field (name "TOLERANCE") "1%") (field (name "MANUFACTURER") "Multi-Sourced"))
      (libsource (lib "altium-import") (part "root_0_RES1_"))
    )
    (comp (ref "R28A")
      (value "0R")
      (footprint "R0603")
      (description "PS SMD RES. 0OHM 1/10W 5% 0603")
      (fields (field (name "TOLERANCE") "1%") (field (name "MANUFACTURER") "Multi-Sourced"))
      (libsource (lib "altium-import") (part "root_0_RES1_"))
    )
    (comp (ref "R29A")
      (value "10R")
      (footprint "R1206")
      (description "PS SMD RES. 10OHM 1/4W 5% 1206")
      (fields (field (name "TOLERANCE") "1%") (field (name "MANUFACTURER") "Multi-Sourced"))
      (libsource (lib "altium-import") (part "root_1_mirrored_RES1_"))
    )
    (comp (ref "R30A")
      (value "3.3R")
      (footprint "R0603")
      (description "PS SMD RES. 3.3OHM 1/10W 1% 0603")
      (fields (field (name "TOLERANCE") "1%") (field (name "MANUFACTURER") "Multi-Sourced"))
      (libsource (lib "altium-import") (part "root_1_mirrored_RES1_"))
    )
    (comp (ref "R31A")
      (value "10R")
      (footprint "R0603")
      (description "PS SMD RES. 10OHM 1/10W 5% 0603")
      (fields (field (name "TOLERANCE") "1%") (field (name "MANUFACTURER") "Multi-Sourced"))
      (libsource (lib "altium-import") (part "root_2_RES1_"))
    )
    (comp (ref "R32A")
      (value "10R")
      (footprint "R0603")
      (description "PS SMD RES. 10OHM 1/10W 5% 0603")
      (fields (field (name "TOLERANCE") "1%") (field (name "MANUFACTURER") "Multi-Sourced"))
      (libsource (lib "altium-import") (part "root_2_RES1_"))
    )
    (comp (ref "R33A")
      (value "10R")
      (footprint "R1206")
      (description "PS SMD RES. 10OHM 1/4W 5% 1206")
      (fields (field (name "TOLERANCE") "1%") (field (name "MANUFACTURER") "Multi-Sourced"))
      (libsource (lib "altium-import") (part "root_1_mirrored_RES1_"))
    )
    (comp (ref "R34A")
      (value "3.3R")
      (footprint "R0603")
      (description "PS SMD RES. 3.3OHM 1/10W 1% 0603")
      (fields (field (name "TOLERANCE") "1%") (field (name "MANUFACTURER") "Multi-Sourced"))
      (libsource (lib "altium-import") (part "root_3_mirrored_RES1_"))
    )
    (comp (ref "R35A")
      (value "4.7k")
      (footprint "R0603")
      (description "PS SMD RES. 4.7KOHM 1/10W 1% 0603")
      (fields (field (name "TOLERANCE") "1%") (field (name "MANUFACTURER") "Multi-Sourced"))
      (libsource (lib "altium-import") (part "root_0_RES1_"))
    )
    (comp (ref "R37A")
      (value "10k")
      (footprint "R0603")
      (description "PS SMD RES. 10KOHM 1/10W 1% 0603")
      (fields (field (name "TOLERANCE") "1%") (field (name "MANUFACTURER") "Multi-Sourced"))
      (libsource (lib "altium-import") (part "root_0_RES1_"))
    )
    (comp (ref "R38A")
      (value "10k")
      (footprint "R0603")
      (description "PS SMD RES. 10KOHM 1/10W 1% 0603")
      (fields (field (name "TOLERANCE") "1%") (field (name "MANUFACTURER") "Multi-Sourced"))
      (libsource (lib "altium-import") (part "root_0_RES1_"))
    )
    (comp (ref "R39A")
      (value "NC")
      (footprint "R0603")
      (description "PS SMD RES. 10KOHM 1/10W 1% 0603")
      (fields (field (name "TOLERANCE") "1%") (field (name "MANUFACTURER") "Multi-Sourced"))
      (libsource (lib "altium-import") (part "root_0_RES1_"))
    )
    (comp (ref "Teufel_ASM_Label1A")
      (value "~")
      (footprint "Teufel_ASM_Rev")
      (description "Teufel_ASM_Rev")
      (libsource (lib "altium-import") (part "root_0_Teufel_ASM_Label_"))
    )
    (comp (ref "Teufel_Copyright1A")
      (value "~")
      (footprint "TEUFEL_COPYRIGHT")
      (description "Teufel_Copyright_Year")
      (libsource (lib "altium-import") (part "root_0_Teufel_Copyright_"))
    )
    (comp (ref "Teufel_PCB_Label1A")
      (value "~")
      (footprint "Teufel_PCB_Rev")
      (description "Teufel_PCB_Label")
      (libsource (lib "altium-import") (part "root_0_Teufel_PCB_Label_"))
    )
    (comp (ref "Teufel_PCB_Logo1A")
      (value "-2.1")
      (footprint "Teufel_NoLogo")
      (description "Teufel PCB NoLogo")
      (libsource (lib "altium-import") (part "root_0_Teufel NoLogo_"))
    )
    (comp (ref "TP1A")
      (value "TP_T_60_40")
      (footprint "TP_T_60_40")
      (description "Test Point")
      (libsource (lib "altium-import") (part "root_1_TP_"))
    )
    (comp (ref "TP2A")
      (value "TP_T_60_40")
      (footprint "TP_T_60_40")
      (description "Test Point")
      (libsource (lib "altium-import") (part "root_1_TP_"))
    )
    (comp (ref "TP3A")
      (value "TP12")
      (footprint "TP120")
      (description "Test Point")
      (libsource (lib "altium-import") (part "root_2_TP_"))
    )
    (comp (ref "TP4A")
      (value "TP12")
      (footprint "TP120")
      (description "Test Point")
      (libsource (lib "altium-import") (part "root_2_TP_"))
    )
    (comp (ref "TP5A")
      (value "TP12")
      (footprint "TP120")
      (description "Test Point")
      (libsource (lib "altium-import") (part "root_0_TP_"))
    )
    (comp (ref "TP6A")
      (value "TP12")
      (footprint "TP120")
      (description "Test Point")
      (libsource (lib "altium-import") (part "root_0_TP_"))
    )
    (comp (ref "TP7A")
      (value "TP12")
      (footprint "TP120")
      (description "Test Point")
      (libsource (lib "altium-import") (part "root_2_TP_"))
    )
    (comp (ref "TP8A")
      (value "TP12")
      (footprint "TP120")
      (description "Test Point")
      (libsource (lib "altium-import") (part "root_0_TP_"))
    )
    (comp (ref "TP9A")
      (value "TP12")
      (footprint "TP120")
      (description "Test Point")
      (libsource (lib "altium-import") (part "root_0_TP_"))
    )
    (comp (ref "TP10A")
      (value "TP12")
      (footprint "TP120")
      (description "Test Point")
      (libsource (lib "altium-import") (part "root_2_TP_"))
    )
    (comp (ref "TP11A")
      (value "TP12")
      (footprint "TP120")
      (description "Test Point")
      (libsource (lib "altium-import") (part "root_0_TP_"))
    )
    (comp (ref "TP12A")
      (value "TP12")
      (footprint "TP120")
      (description "Test Point")
      (libsource (lib "altium-import") (part "root_2_TP_"))
    )
    (comp (ref "TP13A")
      (value "TP12")
      (footprint "TP120")
      (description "Test Point")
      (libsource (lib "altium-import") (part "root_2_TP_"))
    )
    (comp (ref "TP14A")
      (value "TP12")
      (footprint "TP120")
      (description "Test Point")
      (libsource (lib "altium-import") (part "root_0_TP_"))
    )
    (comp (ref "TP15A")
      (value "TP12")
      (footprint "TP120")
      (description "Test Point")
      (libsource (lib "altium-import") (part "root_0_TP_"))
    )
    (comp (ref "TP16A")
      (value "TP12")
      (footprint "TP120")
      (description "Test Point")
      (libsource (lib "altium-import") (part "root_2_TP_"))
    )
    (comp (ref "TP17A")
      (value "TP12")
      (footprint "TP120")
      (description "Test Point")
      (libsource (lib "altium-import") (part "root_0_TP_"))
    )
    (comp (ref "TP18A")
      (value "TP12")
      (footprint "TP120")
      (description "Test Point")
      (libsource (lib "altium-import") (part "root_2_TP_"))
    )
    (comp (ref "TP19A")
      (value "TP12")
      (footprint "TP120")
      (description "Test Point")
      (libsource (lib "altium-import") (part "root_0_TP_"))
    )
    (comp (ref "TP20A")
      (value "TP12")
      (footprint "TP120")
      (description "Test Point")
      (libsource (lib "altium-import") (part "root_0_TP_"))
    )
    (comp (ref "TP21A")
      (value "TP12")
      (footprint "TP120")
      (description "Test Point")
      (libsource (lib "altium-import") (part "root_2_TP_"))
    )
    (comp (ref "TP22A")
      (value "TP12")
      (footprint "TP120")
      (description "Test Point")
      (libsource (lib "altium-import") (part "root_0_TP_"))
    )
    (comp (ref "TP23A")
      (value "TP12")
      (footprint "TP120")
      (description "Test Point")
      (libsource (lib "altium-import") (part "root_0_TP_"))
    )
    (comp (ref "TP24A")
      (value "TP12")
      (footprint "TP120")
      (description "Test Point")
      (libsource (lib "altium-import") (part "root_2_TP_"))
    )
    (comp (ref "U1A")
      (value "~")
      (footprint "QFN32_500X500X100_50_P350X350")
      (description "GP SMD IC 32P VQFN TAS5825PRHBR TI")
      (fields (field (name "MANUFACTURER") "[TI]") (field (name "PART_NUMBER") "TAS5825PRHBR"))
      (libsource (lib "altium-import") (part "root_0_TAS5825P_"))
    )
    (comp (ref "U2A")
      (value "~")
      (footprint "TSSOP28(PWP)")
      (description "GP SMD IC 28P HTSSOP TAS5805MPWPR TI")
      (fields (field (name "MANUFACTURER") "[TI]") (field (name "PART_NUMBER") "TAS5805MPWPR"))
      (libsource (lib "altium-import") (part "root_0_TAS5805M_"))
    )
  )
  (nets
    (net (code "1") (name "/Amp_Ver") (class "Default")
      (node (ref "P3A") (pin "17") (pinfunction "17_17") (pintype "passive"))
      (node (ref "R15A") (pin "2") (pinfunction "2_2") (pintype "passive"))
      (node (ref "R16A") (pin "1") (pinfunction "1_1") (pintype "passive"))
      (node (ref "TP18A") (pin "1") (pinfunction "1_1") (pintype "passive"))
    )
    (net (code "2") (name "/BatVCC") (class "Default")
      (node (ref "C66A") (pin "1") (pinfunction "1_1") (pintype "passive"))
      (node (ref "P2A") (pin "5") (pinfunction "5_5") (pintype "passive"))
      (node (ref "P3A") (pin "9") (pinfunction "9_9") (pintype "passive"))
      (node (ref "TP13A") (pin "1") (pinfunction "1_1") (pintype "passive"))
      (node (ref "TP7A") (pin "1") (pinfunction "1_1") (pintype "passive"))
    )
    (net (code "3") (name "/C_Open") (class "Default")
      (node (ref "C69A") (pin "1") (pinfunction "1_1") (pintype "passive"))
      (node (ref "P2A") (pin "6") (pinfunction "6_6") (pintype "passive"))
      (node (ref "P3A") (pin "11") (pinfunction "11_11") (pintype "passive"))
      (node (ref "TP16A") (pin "1") (pinfunction "1_1") (pintype "passive"))
      (node (ref "TP6A") (pin "1") (pinfunction "1_1") (pintype "passive"))
    )
    (net (code "4") (name "/Env_Track") (class "Default")
      (node (ref "P3A") (pin "14") (pinfunction "14_14") (pintype "passive"))
      (node (ref "R2A") (pin "2") (pinfunction "2_2") (pintype "passive"))
      (node (ref "R38A") (pin "2") (pinfunction "2_2") (pintype "passive"))
      (node (ref "TP15A") (pin "1") (pinfunction "1_1") (pintype "passive"))
    )
    (net (code "5") (name "/I2S_BCLK") (class "Default")
      (node (ref "P3A") (pin "18") (pinfunction "18_18") (pintype "passive"))
      (node (ref "R25A") (pin "1") (pinfunction "1_1") (pintype "passive"))
      (node (ref "R5A") (pin "1") (pinfunction "1_1") (pintype "passive"))
      (node (ref "TP19A") (pin "1") (pinfunction "1_1") (pintype "passive"))
    )
    (net (code "6") (name "/I2S_DATA") (class "Default")
      (node (ref "P3A") (pin "16") (pinfunction "16_16") (pintype "passive"))
      (node (ref "R23A") (pin "1") (pinfunction "1_1") (pintype "passive"))
      (node (ref "R3A") (pin "1") (pinfunction "1_1") (pintype "passive"))
      (node (ref "TP17A") (pin "1") (pinfunction "1_1") (pintype "passive"))
    )
    (net (code "7") (name "/I2S_LRCK") (class "Default")
      (node (ref "P3A") (pin "20") (pinfunction "20_20") (pintype "passive"))
      (node (ref "R26A") (pin "1") (pinfunction "1_1") (pintype "passive"))
      (node (ref "R8A") (pin "1") (pinfunction "1_1") (pintype "passive"))
      (node (ref "TP20A") (pin "1") (pinfunction "1_1") (pintype "passive"))
    )
    (net (code "8") (name "/SCL") (class "Default")
      (node (ref "P3A") (pin "23") (pinfunction "23_23") (pintype "passive"))
      (node (ref "R12A") (pin "1") (pinfunction "1_1") (pintype "passive"))
      (node (ref "R28A") (pin "1") (pinfunction "1_1") (pintype "passive"))
      (node (ref "TP24A") (pin "1") (pinfunction "1_1") (pintype "passive"))
    )
    (net (code "9") (name "/SDA") (class "Default")
      (node (ref "P3A") (pin "21") (pinfunction "21_21") (pintype "passive"))
      (node (ref "R27A") (pin "1") (pinfunction "1_1") (pintype "passive"))
      (node (ref "R9A") (pin "1") (pinfunction "1_1") (pintype "passive"))
      (node (ref "TP21A") (pin "1") (pinfunction "1_1") (pintype "passive"))
    )
    (net (code "10") (name "/SW_N") (class "Default")
      (node (ref "C11A") (pin "1") (pinfunction "1_1") (pintype "passive"))
      (node (ref "C12A") (pin "1") (pinfunction "1_1") (pintype "passive"))
      (node (ref "C14A") (pin "2") (pinfunction "2_2") (pintype "passive"))
      (node (ref "C67A") (pin "1") (pinfunction "1_1") (pintype "passive"))
      (node (ref "L2A") (pin "2") (pinfunction "2_2") (pintype "passive"))
      (node (ref "P2A") (pin "1") (pinfunction "1_1") (pintype "passive"))
      (node (ref "P2A") (pin "3") (pinfunction "3_3") (pintype "passive"))
      (node (ref "TP4A") (pin "1") (pinfunction "1_1") (pintype "passive"))
    )
    (net (code "11") (name "/SW_P") (class "Default")
      (node (ref "C3A") (pin "1") (pinfunction "1_1") (pintype "passive"))
      (node (ref "C4A") (pin "1") (pinfunction "1_1") (pintype "passive"))
      (node (ref "C5A") (pin "1") (pinfunction "1_1") (pintype "passive"))
      (node (ref "C68A") (pin "1") (pinfunction "1_1") (pintype "passive"))
      (node (ref "L1A") (pin "2") (pinfunction "2_2") (pintype "passive"))
      (node (ref "P2A") (pin "2") (pinfunction "2_2") (pintype "passive"))
      (node (ref "P2A") (pin "4") (pinfunction "4_4") (pintype "passive"))
      (node (ref "TP5A") (pin "1") (pinfunction "1_1") (pintype "passive"))
    )
    (net (code "12") (name "/TW_L_N") (class "Default")
      (node (ref "C52A") (pin "1") (pinfunction "1_1") (pintype "passive"))
      (node (ref "C53A") (pin "1") (pinfunction "1_1") (pintype "passive"))
      (node (ref "C54A") (pin "1") (pinfunction "1_1") (pintype "passive"))
      (node (ref "C71A") (pin "1") (pinfunction "1_1") (pintype "passive"))
      (node (ref "L5A") (pin "2") (pinfunction "2_2") (pintype "passive"))
      (node (ref "P2A") (pin "10") (pinfunction "10_10") (pintype "passive"))
      (node (ref "TP11A") (pin "1") (pinfunction "1_1") (pintype "passive"))
    )
    (net (code "13") (name "/TW_L_P") (class "Default")
      (node (ref "C60A") (pin "1") (pinfunction "1_1") (pintype "passive"))
      (node (ref "C61A") (pin "1") (pinfunction "1_1") (pintype "passive"))
      (node (ref "C63A") (pin "2") (pinfunction "2_2") (pintype "passive"))
      (node (ref "C70A") (pin "1") (pinfunction "1_1") (pintype "passive"))
      (node (ref "L6A") (pin "2") (pinfunction "2_2") (pintype "passive"))
      (node (ref "P2A") (pin "8") (pinfunction "8_8") (pintype "passive"))
      (node (ref "TP8A") (pin "1") (pinfunction "1_1") (pintype "passive"))
    )
    (net (code "14") (name "/TW_R_N") (class "Default")
      (node (ref "C38A") (pin "1") (pinfunction "1_1") (pintype "passive"))
      (node (ref "C39A") (pin "1") (pinfunction "1_1") (pintype "passive"))
      (node (ref "C44A") (pin "2") (pinfunction "2_2") (pintype "passive"))
      (node (ref "C64A") (pin "1") (pinfunction "1_1") (pintype "passive"))
      (node (ref "L4A") (pin "2") (pinfunction "2_2") (pintype "passive"))
      (node (ref "P2A") (pin "9") (pinfunction "9_9") (pintype "passive"))
      (node (ref "TP12A") (pin "1") (pinfunction "1_1") (pintype "passive"))
    )
    (net (code "15") (name "/TW_R_P") (class "Default")
      (node (ref "C33A") (pin "1") (pinfunction "1_1") (pintype "passive"))
      (node (ref "C34A") (pin "1") (pinfunction "1_1") (pintype "passive"))
      (node (ref "C35A") (pin "1") (pinfunction "1_1") (pintype "passive"))
      (node (ref "C65A") (pin "1") (pinfunction "1_1") (pintype "passive"))
      (node (ref "L3A") (pin "2") (pinfunction "2_2") (pintype "passive"))
      (node (ref "P2A") (pin "7") (pinfunction "7_7") (pintype "passive"))
      (node (ref "TP10A") (pin "1") (pinfunction "1_1") (pintype "passive"))
    )
    (net (code "16") (name "/~{Amp_PDN}") (class "Default")
      (node (ref "P3A") (pin "24") (pinfunction "24_24") (pintype "passive"))
      (node (ref "R13A") (pin "2") (pinfunction "2_2") (pintype "passive"))
      (node (ref "R18A") (pin "1") (pinfunction "1_1") (pintype "passive"))
      (node (ref "R31A") (pin "2") (pinfunction "2_2") (pintype "passive"))
      (node (ref "R39A") (pin "2") (pinfunction "2_2") (pintype "passive"))
      (node (ref "TP23A") (pin "1") (pinfunction "1_1") (pintype "passive"))
    )
    (net (code "17") (name "/~{Amp_SwFlt}") (class "Default")
      (node (ref "P3A") (pin "12") (pinfunction "12_12") (pintype "passive"))
      (node (ref "R1A") (pin "2") (pinfunction "2_2") (pintype "passive"))
      (node (ref "R37A") (pin "2") (pinfunction "2_2") (pintype "passive"))
      (node (ref "TP14A") (pin "1") (pinfunction "1_1") (pintype "passive"))
    )
    (net (code "18") (name "/~{Amp_TwFlt}") (class "Default")
      (node (ref "P3A") (pin "22") (pinfunction "22_22") (pintype "passive"))
      (node (ref "R32A") (pin "2") (pinfunction "2_2") (pintype "passive"))
      (node (ref "TP22A") (pin "1") (pinfunction "1_1") (pintype "passive"))
    )
    (net (code "19") (name "3V3_STB") (class "Default")
      (node (ref "P3A") (pin "10") (pinfunction "10_10") (pintype "passive"))
      (node (ref "R17A") (pin "2") (pinfunction "2_2") (pintype "passive"))
      (node (ref "R4A") (pin "2") (pinfunction "2_2") (pintype "passive"))
    )
    (net (code "20") (name "3V3_SW") (class "Default")
      (node (ref "C25A") (pin "1") (pinfunction "1_1") (pintype "passive"))
      (node (ref "C26A") (pin "1") (pinfunction "1_1") (pintype "passive"))
      (node (ref "C7A") (pin "1") (pinfunction "1_1") (pintype "passive"))
      (node (ref "C8A") (pin "1") (pinfunction "1_1") (pintype "passive"))
      (node (ref "FB1A") (pin "2") (pinfunction "2_2") (pintype "passive"))
      (node (ref "R15A") (pin "1") (pinfunction "1_1") (pintype "passive"))
      (node (ref "R37A") (pin "1") (pinfunction "1_1") (pintype "passive"))
      (node (ref "R38A") (pin "1") (pinfunction "1_1") (pintype "passive"))
      (node (ref "R39A") (pin "1") (pinfunction "1_1") (pintype "passive"))
      (node (ref "TP1A") (pin "1") (pinfunction "1_1") (pintype "passive"))
      (node (ref "U1A") (pin "6") (pinfunction "DVDD_6") (pintype "passive"))
    )
    (net (code "21") (name "3V3_TW") (class "Default")
      (node (ref "C30A") (pin "1") (pinfunction "1_1") (pintype "passive"))
      (node (ref "C31A") (pin "1") (pinfunction "1_1") (pintype "passive"))
      (node (ref "C56A") (pin "1") (pinfunction "1_1") (pintype "passive"))
      (node (ref "C57A") (pin "1") (pinfunction "1_1") (pintype "passive"))
      (node (ref "FB4A") (pin "2") (pinfunction "2_2") (pintype "passive"))
      (node (ref "R35A") (pin "1") (pinfunction "1_1") (pintype "passive"))
      (node (ref "TP2A") (pin "1") (pinfunction "1_1") (pintype "passive"))
      (node (ref "U2A") (pin "2") (pinfunction "DVDD_2") (pintype "passive"))
    )
    (net (code "22") (name "24V") (class "Default")
      (node (ref "FB2A") (pin "1") (pinfunction "1_1") (pintype "passive"))
      (node (ref "FB3A") (pin "1") (pinfunction "1_1") (pintype "passive"))
      (node (ref "FB5A") (pin "1") (pinfunction "1_1") (pintype "passive"))
      (node (ref "FB6A") (pin "2") (pinfunction "2_2") (pintype "passive"))
      (node (ref "P3A") (pin "1") (pinfunction "1_1") (pintype "passive"))
      (node (ref "P3A") (pin "2") (pinfunction "2_2") (pintype "passive"))
      (node (ref "P3A") (pin "3") (pinfunction "3_3") (pintype "passive"))
      (node (ref "P3A") (pin "4") (pinfunction "4_4") (pintype "passive"))
      (node (ref "TP3A") (pin "1") (pinfunction "1_1") (pintype "passive"))
      (node (ref "TP9A") (pin "1") (pinfunction "1_1") (pintype "passive"))
    )
    (net (code "23") (name "GND") (class "Default")
      (node (ref "C11A") (pin "2") (pinfunction "2_2") (pintype "passive"))
      (node (ref "C12A") (pin "2") (pinfunction "2_2") (pintype "passive"))
      (node (ref "C16A") (pin "2") (pinfunction "2_2") (pintype "passive"))
      (node (ref "C17A") (pin "2") (pinfunction "2_2") (pintype "passive"))
      (node (ref "C18A") (pin "2") (pinfunction "2_2") (pintype "passive"))
      (node (ref "C19A") (pin "2") (pinfunction "2_2") (pintype "passive"))
      (node (ref "C20A") (pin "2") (pinfunction "2_2") (pintype "passive"))
      (node (ref "C21A") (pin "2") (pinfunction "2_2") (pintype "passive"))
      (node (ref "C22A") (pin "2") (pinfunction "2_2") (pintype "passive"))
      (node (ref "C23A") (pin "2") (pinfunction "2_2") (pintype "passive"))
      (node (ref "C24A") (pin "1") (pinfunction "1_1") (pintype "passive"))
      (node (ref "C25A") (pin "2") (pinfunction "2_2") (pintype "passive"))
      (node (ref "C26A") (pin "2") (pinfunction "2_2") (pintype "passive"))
      (node (ref "C27A") (pin "1") (pinfunction "1_1") (pintype "passive"))
      (node (ref "C28A") (pin "1") (pinfunction "1_1") (pintype "passive"))
      (node (ref "C29A") (pin "2") (pinfunction "2_2") (pintype "passive"))
      (node (ref "C30A") (pin "2") (pinfunction "2_2") (pintype "passive"))
      (node (ref "C31A") (pin "2") (pinfunction "2_2") (pintype "passive"))
      (node (ref "C34A") (pin "2") (pinfunction "2_2") (pintype "passive"))
      (node (ref "C35A") (pin "2") (pinfunction "2_2") (pintype "passive"))
      (node (ref "C37A") (pin "2") (pinfunction "2_2") (pintype "passive"))
      (node (ref "C38A") (pin "2") (pinfunction "2_2") (pintype "passive"))
      (node (ref "C39A") (pin "2") (pinfunction "2_2") (pintype "passive"))
      (node (ref "C40A") (pin "2") (pinfunction "2_2") (pintype "passive"))
      (node (ref "C41A") (pin "2") (pinfunction "2_2") (pintype "passive"))
      (node (ref "C42A") (pin "2") (pinfunction "2_2") (pintype "passive"))
      (node (ref "C46A") (pin "2") (pinfunction "2_2") (pintype "passive"))
      (node (ref "C47A") (pin "2") (pinfunction "2_2") (pintype "passive"))
      (node (ref "C48A") (pin "2") (pinfunction "2_2") (pintype "passive"))
      (node (ref "C49A") (pin "2") (pinfunction "2_2") (pintype "passive"))
      (node (ref "C4A") (pin "2") (pinfunction "2_2") (pintype "passive"))
      (node (ref "C53A") (pin "2") (pinfunction "2_2") (pintype "passive"))
      (node (ref "C54A") (pin "2") (pinfunction "2_2") (pintype "passive"))
      (node (ref "C55A") (pin "1") (pinfunction "1_1") (pintype "passive"))
      (node (ref "C56A") (pin "2") (pinfunction "2_2") (pintype "passive"))
      (node (ref "C57A") (pin "2") (pinfunction "2_2") (pintype "passive"))
      (node (ref "C59A") (pin "1") (pinfunction "1_1") (pintype "passive"))
      (node (ref "C5A") (pin "2") (pinfunction "2_2") (pintype "passive"))
      (node (ref "C60A") (pin "2") (pinfunction "2_2") (pintype "passive"))
      (node (ref "C61A") (pin "2") (pinfunction "2_2") (pintype "passive"))
      (node (ref "C64A") (pin "2") (pinfunction "2_2") (pintype "passive"))
      (node (ref "C65A") (pin "2") (pinfunction "2_2") (pintype "passive"))
      (node (ref "C66A") (pin "2") (pinfunction "2_2") (pintype "passive"))
      (node (ref "C67A") (pin "2") (pinfunction "2_2") (pintype "passive"))
      (node (ref "C68A") (pin "2") (pinfunction "2_2") (pintype "passive"))
      (node (ref "C69A") (pin "2") (pinfunction "2_2") (pintype "passive"))
      (node (ref "C6A") (pin "2") (pinfunction "2_2") (pintype "passive"))
      (node (ref "C70A") (pin "2") (pinfunction "2_2") (pintype "passive"))
      (node (ref "C71A") (pin "2") (pinfunction "2_2") (pintype "passive"))
      (node (ref "C7A") (pin "2") (pinfunction "2_2") (pintype "passive"))
      (node (ref "C8A") (pin "2") (pinfunction "2_2") (pintype "passive"))
      (node (ref "MH1A") (pin "1") (pinfunction "1_1") (pintype "passive"))
      (node (ref "MH2A") (pin "1") (pinfunction "1_1") (pintype "passive"))
      (node (ref "MH3A") (pin "1") (pinfunction "1_1") (pintype "passive"))
      (node (ref "MH4A") (pin "1") (pinfunction "1_1") (pintype "passive"))
      (node (ref "P3A") (pin "13") (pinfunction "13_13") (pintype "passive"))
      (node (ref "P3A") (pin "15") (pinfunction "15_15") (pintype "passive"))
      (node (ref "P3A") (pin "19") (pinfunction "19_19") (pintype "passive"))
      (node (ref "P3A") (pin "5") (pinfunction "5_5") (pintype "passive"))
      (node (ref "P3A") (pin "6") (pinfunction "6_6") (pintype "passive"))
      (node (ref "P3A") (pin "7") (pinfunction "7_7") (pintype "passive"))
      (node (ref "P3A") (pin "8") (pinfunction "8_8") (pintype "passive"))
      (node (ref "R10A") (pin "1") (pinfunction "1_1") (pintype "passive"))
      (node (ref "R11A") (pin "2") (pinfunction "2_2") (pintype "passive"))
      (node (ref "R14A") (pin "1") (pinfunction "1_1") (pintype "passive"))
      (node (ref "R16A") (pin "2") (pinfunction "2_2") (pintype "passive"))
      (node (ref "R18A") (pin "2") (pinfunction "2_2") (pintype "passive"))
      (node (ref "R19A") (pin "2") (pinfunction "2_2") (pintype "passive"))
      (node (ref "R20A") (pin "2") (pinfunction "2_2") (pintype "passive"))
      (node (ref "R21A") (pin "2") (pinfunction "2_2") (pintype "passive"))
      (node (ref "R22A") (pin "1") (pinfunction "1_1") (pintype "passive"))
      (node (ref "R24A") (pin "2") (pinfunction "2_2") (pintype "passive"))
      (node (ref "R29A") (pin "2") (pinfunction "2_2") (pintype "passive"))
      (node (ref "R30A") (pin "2") (pinfunction "2_2") (pintype "passive"))
      (node (ref "R33A") (pin "1") (pinfunction "1_1") (pintype "passive"))
      (node (ref "R34A") (pin "2") (pinfunction "2_2") (pintype "passive"))
      (node (ref "R6A") (pin "2") (pinfunction "2_2") (pintype "passive"))
      (node (ref "R7A") (pin "2") (pinfunction "2_2") (pintype "passive"))
      (node (ref "U1A") (pin "0") (pinfunction "T_Pad_0") (pintype "passive"))
      (node (ref "U1A") (pin "20") (pinfunction "AGND_20") (pintype "passive"))
      (node (ref "U1A") (pin "25") (pinfunction "PGND_25") (pintype "passive"))
      (node (ref "U1A") (pin "26") (pinfunction "PGND_26") (pintype "passive"))
      (node (ref "U1A") (pin "31") (pinfunction "PGND_31") (pintype "passive"))
      (node (ref "U1A") (pin "32") (pinfunction "PGND_32") (pintype "passive"))
      (node (ref "U1A") (pin "5") (pinfunction "DGND_5") (pintype "passive"))
      (node (ref "U2A") (pin "0") (pinfunction "T_PAD_0") (pintype "passive"))
      (node (ref "U2A") (pin "1") (pinfunction "DGND_1") (pintype "passive"))
      (node (ref "U2A") (pin "14") (pinfunction "AGND_14") (pintype "passive"))
      (node (ref "U2A") (pin "19") (pinfunction "PGND_19") (pintype "passive"))
      (node (ref "U2A") (pin "24") (pinfunction "PGND_24") (pintype "passive"))
      (node (ref "U2A") (pin "5") (pinfunction "DGND_5") (pintype "passive"))
    )
    (net (code "24") (name "Net-(C2A-Pad1)") (class "Default")
      (node (ref "C2A") (pin "1") (pinfunction "1_1") (pintype "passive"))
      (node (ref "R6A") (pin "1") (pinfunction "1_1") (pintype "passive"))
    )
    (net (code "25") (name "Net-(C3A-Pad2)") (class "Default")
      (node (ref "C3A") (pin "2") (pinfunction "2_2") (pintype "passive"))
      (node (ref "R7A") (pin "1") (pinfunction "1_1") (pintype "passive"))
    )
    (net (code "26") (name "Net-(C6A-Pad1)") (class "Default")
      (node (ref "C6A") (pin "1") (pinfunction "1_1") (pintype "passive"))
      (node (ref "FB1A") (pin "1") (pinfunction "1_1") (pintype "passive"))
      (node (ref "R4A") (pin "1") (pinfunction "1_1") (pintype "passive"))
    )
    (net (code "27") (name "Net-(C13A-Pad2)") (class "Default")
      (node (ref "C13A") (pin "2") (pinfunction "2_2") (pintype "passive"))
      (node (ref "R10A") (pin "2") (pinfunction "2_2") (pintype "passive"))
    )
    (net (code "28") (name "Net-(C14A-Pad1)") (class "Default")
      (node (ref "C14A") (pin "1") (pinfunction "1_1") (pintype "passive"))
      (node (ref "R11A") (pin "1") (pinfunction "1_1") (pintype "passive"))
    )
    (net (code "29") (name "Net-(C16A-Pad1)") (class "Default")
      (node (ref "C16A") (pin "1") (pinfunction "1_1") (pintype "passive"))
      (node (ref "C17A") (pin "1") (pinfunction "1_1") (pintype "passive"))
      (node (ref "C18A") (pin "1") (pinfunction "1_1") (pintype "passive"))
      (node (ref "C19A") (pin "1") (pinfunction "1_1") (pintype "passive"))
      (node (ref "FB2A") (pin "2") (pinfunction "2_2") (pintype "passive"))
      (node (ref "U1A") (pin "3") (pinfunction "PVDD_3") (pintype "passive"))
      (node (ref "U1A") (pin "4") (pinfunction "PVDD_4") (pintype "passive"))
    )
    (net (code "30") (name "Net-(C20A-Pad1)") (class "Default")
      (node (ref "C20A") (pin "1") (pinfunction "1_1") (pintype "passive"))
      (node (ref "C21A") (pin "1") (pinfunction "1_1") (pintype "passive"))
      (node (ref "C22A") (pin "1") (pinfunction "1_1") (pintype "passive"))
      (node (ref "C23A") (pin "1") (pinfunction "1_1") (pintype "passive"))
      (node (ref "FB3A") (pin "2") (pinfunction "2_2") (pintype "passive"))
      (node (ref "U1A") (pin "21") (pinfunction "PVDD_21") (pintype "passive"))
      (node (ref "U1A") (pin "22") (pinfunction "PVDD_22") (pintype "passive"))
    )
    (net (code "31") (name "Net-(C29A-Pad1)") (class "Default")
      (node (ref "C29A") (pin "1") (pinfunction "1_1") (pintype "passive"))
      (node (ref "FB4A") (pin "1") (pinfunction "1_1") (pintype "passive"))
      (node (ref "R17A") (pin "1") (pinfunction "1_1") (pintype "passive"))
    )
    (net (code "32") (name "Net-(C32A-Pad1)") (class "Default")
      (node (ref "C32A") (pin "1") (pinfunction "1_1") (pintype "passive"))
      (node (ref "R19A") (pin "1") (pinfunction "1_1") (pintype "passive"))
    )
    (net (code "33") (name "Net-(C33A-Pad2)") (class "Default")
      (node (ref "C33A") (pin "2") (pinfunction "2_2") (pintype "passive"))
      (node (ref "R20A") (pin "1") (pinfunction "1_1") (pintype "passive"))
    )
    (net (code "34") (name "Net-(C37A-Pad1)") (class "Default")
      (node (ref "C37A") (pin "1") (pinfunction "1_1") (pintype "passive"))
      (node (ref "C40A") (pin "1") (pinfunction "1_1") (pintype "passive"))
      (node (ref "C41A") (pin "1") (pinfunction "1_1") (pintype "passive"))
      (node (ref "C42A") (pin "1") (pinfunction "1_1") (pintype "passive"))
      (node (ref "FB5A") (pin "2") (pinfunction "2_2") (pintype "passive"))
      (node (ref "U2A") (pin "15") (pinfunction "PVDD_15") (pintype "passive"))
      (node (ref "U2A") (pin "16") (pinfunction "PVDD_16") (pintype "passive"))
    )
    (net (code "35") (name "Net-(C43A-Pad2)") (class "Default")
      (node (ref "C43A") (pin "2") (pinfunction "2_2") (pintype "passive"))
      (node (ref "R22A") (pin "2") (pinfunction "2_2") (pintype "passive"))
    )
    (net (code "36") (name "Net-(C44A-Pad1)") (class "Default")
      (node (ref "C44A") (pin "1") (pinfunction "1_1") (pintype "passive"))
      (node (ref "R24A") (pin "1") (pinfunction "1_1") (pintype "passive"))
    )
    (net (code "37") (name "Net-(C46A-Pad1)") (class "Default")
      (node (ref "C46A") (pin "1") (pinfunction "1_1") (pintype "passive"))
      (node (ref "C47A") (pin "1") (pinfunction "1_1") (pintype "passive"))
      (node (ref "C48A") (pin "1") (pinfunction "1_1") (pintype "passive"))
      (node (ref "C49A") (pin "1") (pinfunction "1_1") (pintype "passive"))
      (node (ref "FB6A") (pin "1") (pinfunction "1_1") (pintype "passive"))
      (node (ref "U2A") (pin "27") (pinfunction "PVDD_27") (pintype "passive"))
      (node (ref "U2A") (pin "28") (pinfunction "PVDD_28") (pintype "passive"))
    )
    (net (code "38") (name "Net-(C51A-Pad1)") (class "Default")
      (node (ref "C51A") (pin "1") (pinfunction "1_1") (pintype "passive"))
      (node (ref "R29A") (pin "1") (pinfunction "1_1") (pintype "passive"))
    )
    (net (code "39") (name "Net-(C52A-Pad2)") (class "Default")
      (node (ref "C52A") (pin "2") (pinfunction "2_2") (pintype "passive"))
      (node (ref "R30A") (pin "1") (pinfunction "1_1") (pintype "passive"))
    )
    (net (code "40") (name "Net-(C62A-Pad2)") (class "Default")
      (node (ref "C62A") (pin "2") (pinfunction "2_2") (pintype "passive"))
      (node (ref "R33A") (pin "2") (pinfunction "2_2") (pintype "passive"))
    )
    (net (code "41") (name "Net-(C63A-Pad1)") (class "Default")
      (node (ref "C63A") (pin "1") (pinfunction "1_1") (pintype "passive"))
      (node (ref "R34A") (pin "1") (pinfunction "1_1") (pintype "passive"))
    )
    (net (code "42") (name "Net-(U1A-ADR)") (class "Default")
      (node (ref "R14A") (pin "2") (pinfunction "2_2") (pintype "passive"))
      (node (ref "U1A") (pin "8") (pinfunction "ADR_8") (pintype "passive"))
    )
    (net (code "43") (name "Net-(U1A-AVDD)") (class "Default")
      (node (ref "C28A") (pin "2") (pinfunction "2_2") (pintype "passive"))
      (node (ref "U1A") (pin "19") (pinfunction "AVDD_19") (pintype "passive"))
    )
    (net (code "44") (name "Net-(U1A-BST_A+)") (class "Default")
      (node (ref "C1A") (pin "2") (pinfunction "2_2") (pintype "passive"))
      (node (ref "U1A") (pin "1") (pinfunction "BST_A+_1") (pintype "passive"))
    )
    (net (code "45") (name "Net-(U1A-BST_A-)") (class "Default")
      (node (ref "C9A") (pin "1") (pinfunction "1_1") (pintype "passive"))
      (node (ref "U1A") (pin "29") (pinfunction "BST_A-_29") (pintype "passive"))
    )
    (net (code "46") (name "Net-(U1A-BST_B+)") (class "Default")
      (node (ref "C15A") (pin "1") (pinfunction "1_1") (pintype "passive"))
      (node (ref "U1A") (pin "24") (pinfunction "BST_B+_24") (pintype "passive"))
    )
    (net (code "47") (name "Net-(U1A-BST_B-)") (class "Default")
      (node (ref "C10A") (pin "2") (pinfunction "2_2") (pintype "passive"))
      (node (ref "U1A") (pin "28") (pinfunction "BST_B-_28") (pintype "passive"))
    )
    (net (code "48") (name "Net-(U1A-GPIO0)") (class "Default")
      (node (ref "R1A") (pin "1") (pinfunction "1_1") (pintype "passive"))
      (node (ref "U1A") (pin "9") (pinfunction "GPIO0_9") (pintype "passive"))
    )
    (net (code "49") (name "Net-(U1A-GPIO1)") (class "Default")
      (node (ref "R2A") (pin "1") (pinfunction "1_1") (pintype "passive"))
      (node (ref "U1A") (pin "10") (pinfunction "GPIO1_10") (pintype "passive"))
    )
    (net (code "50") (name "Net-(U1A-GVDD)") (class "Default")
      (node (ref "C27A") (pin "2") (pinfunction "2_2") (pintype "passive"))
      (node (ref "U1A") (pin "18") (pinfunction "GVDD_18") (pintype "passive"))
    )
    (net (code "51") (name "Net-(U1A-LRCLK)") (class "Default")
      (node (ref "R8A") (pin "2") (pinfunction "2_2") (pintype "passive"))
      (node (ref "U1A") (pin "12") (pinfunction "LRCLK_12") (pintype "passive"))
    )
    (net (code "52") (name "Net-(U1A-OUT_A+)") (class "Default")
      (node (ref "C1A") (pin "1") (pinfunction "1_1") (pintype "passive"))
      (node (ref "C2A") (pin "2") (pinfunction "2_2") (pintype "passive"))
      (node (ref "C9A") (pin "2") (pinfunction "2_2") (pintype "passive"))
      (node (ref "L1A") (pin "1") (pinfunction "1_1") (pintype "passive"))
      (node (ref "U1A") (pin "2") (pinfunction "OUT_A+_2") (pintype "passive"))
      (node (ref "U1A") (pin "30") (pinfunction "OUT_A-_30") (pintype "passive"))
    )
    (net (code "53") (name "Net-(U1A-OUT_B+)") (class "Default")
      (node (ref "C10A") (pin "1") (pinfunction "1_1") (pintype "passive"))
      (node (ref "C13A") (pin "1") (pinfunction "1_1") (pintype "passive"))
      (node (ref "C15A") (pin "2") (pinfunction "2_2") (pintype "passive"))
      (node (ref "L2A") (pin "1") (pinfunction "1_1") (pintype "passive"))
      (node (ref "U1A") (pin "23") (pinfunction "OUT_B+_23") (pintype "passive"))
      (node (ref "U1A") (pin "27") (pinfunction "OUT_B-_27") (pintype "passive"))
    )
    (net (code "54") (name "Net-(U1A-PDN)") (class "Default")
      (node (ref "R13A") (pin "1") (pinfunction "1_1") (pintype "passive"))
      (node (ref "U1A") (pin "17") (pinfunction "PDN_17") (pintype "passive"))
    )
    (net (code "55") (name "Net-(U1A-SCL)") (class "Default")
      (node (ref "R12A") (pin "2") (pinfunction "2_2") (pintype "passive"))
      (node (ref "U1A") (pin "16") (pinfunction "SCL_16") (pintype "passive"))
    )
    (net (code "56") (name "Net-(U1A-SCLK)") (class "Default")
      (node (ref "R5A") (pin "2") (pinfunction "2_2") (pintype "passive"))
      (node (ref "U1A") (pin "13") (pinfunction "SCLK_13") (pintype "passive"))
    )
    (net (code "57") (name "Net-(U1A-SDA)") (class "Default")
      (node (ref "R9A") (pin "2") (pinfunction "2_2") (pintype "passive"))
      (node (ref "U1A") (pin "15") (pinfunction "SDA_15") (pintype "passive"))
    )
    (net (code "58") (name "Net-(U1A-SDIN)") (class "Default")
      (node (ref "R3A") (pin "2") (pinfunction "2_2") (pintype "passive"))
      (node (ref "U1A") (pin "14") (pinfunction "SDIN_14") (pintype "passive"))
    )
    (net (code "59") (name "Net-(U1A-VR_DIG)") (class "Default")
      (node (ref "C24A") (pin "2") (pinfunction "2_2") (pintype "passive"))
      (node (ref "U1A") (pin "7") (pinfunction "VR_DIG_7") (pintype "passive"))
    )
    (net (code "60") (name "Net-(U2A-ADR{slash}FAULT)") (class "Default")
      (node (ref "R32A") (pin "1") (pinfunction "1_1") (pintype "passive"))
      (node (ref "R35A") (pin "2") (pinfunction "2_2") (pintype "passive"))
      (node (ref "U2A") (pin "3") (pinfunction "ADR/FAULT_3") (pintype "passive"))
    )
    (net (code "61") (name "Net-(U2A-AVDD)") (class "Default")
      (node (ref "C59A") (pin "2") (pinfunction "2_2") (pintype "passive"))
      (node (ref "U2A") (pin "13") (pinfunction "AVDD_13") (pintype "passive"))
    )
    (net (code "62") (name "Net-(U2A-BST_A+)") (class "Default")
      (node (ref "C36A") (pin "2") (pinfunction "2_2") (pintype "passive"))
      (node (ref "U2A") (pin "25") (pinfunction "BST_A+_25") (pintype "passive"))
    )
    (net (code "63") (name "Net-(U2A-BST_A-)") (class "Default")
      (node (ref "C45A") (pin "1") (pinfunction "1_1") (pintype "passive"))
      (node (ref "U2A") (pin "22") (pinfunction "BST_A-_22") (pintype "passive"))
    )
    (net (code "64") (name "Net-(U2A-BST_B+)") (class "Default")
      (node (ref "C58A") (pin "1") (pinfunction "1_1") (pintype "passive"))
      (node (ref "U2A") (pin "18") (pinfunction "BST_B+_18") (pintype "passive"))
    )
    (net (code "65") (name "Net-(U2A-BST_B-)") (class "Default")
      (node (ref "C50A") (pin "2") (pinfunction "2_2") (pintype "passive"))
      (node (ref "U2A") (pin "21") (pinfunction "BST_B-_21") (pintype "passive"))
    )
    (net (code "66") (name "Net-(U2A-LRCLK)") (class "Default")
      (node (ref "R26A") (pin "2") (pinfunction "2_2") (pintype "passive"))
      (node (ref "U2A") (pin "6") (pinfunction "LRCLK_6") (pintype "passive"))
    )
    (net (code "67") (name "Net-(U2A-OUT_A+)") (class "Default")
      (node (ref "C32A") (pin "2") (pinfunction "2_2") (pintype "passive"))
      (node (ref "C36A") (pin "1") (pinfunction "1_1") (pintype "passive"))
      (node (ref "L3A") (pin "1") (pinfunction "1_1") (pintype "passive"))
      (node (ref "U2A") (pin "26") (pinfunction "OUT_A+_26") (pintype "passive"))
    )
    (net (code "68") (name "Net-(U2A-OUT_A-)") (class "Default")
      (node (ref "C43A") (pin "1") (pinfunction "1_1") (pintype "passive"))
      (node (ref "C45A") (pin "2") (pinfunction "2_2") (pintype "passive"))
      (node (ref "L4A") (pin "1") (pinfunction "1_1") (pintype "passive"))
      (node (ref "U2A") (pin "23") (pinfunction "OUT_A-_23") (pintype "passive"))
    )
    (net (code "69") (name "Net-(U2A-OUT_B+)") (class "Default")
      (node (ref "C58A") (pin "2") (pinfunction "2_2") (pintype "passive"))
      (node (ref "C62A") (pin "1") (pinfunction "1_1") (pintype "passive"))
      (node (ref "L6A") (pin "1") (pinfunction "1_1") (pintype "passive"))
      (node (ref "U2A") (pin "17") (pinfunction "OUT_B+_17") (pintype "passive"))
    )
    (net (code "70") (name "Net-(U2A-OUT_B-)") (class "Default")
      (node (ref "C50A") (pin "1") (pinfunction "1_1") (pintype "passive"))
      (node (ref "C51A") (pin "2") (pinfunction "2_2") (pintype "passive"))
      (node (ref "L5A") (pin "1") (pinfunction "1_1") (pintype "passive"))
      (node (ref "U2A") (pin "20") (pinfunction "OUT_B-_20") (pintype "passive"))
    )
    (net (code "71") (name "Net-(U2A-PDN)") (class "Default")
      (node (ref "R31A") (pin "1") (pinfunction "1_1") (pintype "passive"))
      (node (ref "U2A") (pin "12") (pinfunction "PDN_12") (pintype "passive"))
    )
    (net (code "72") (name "Net-(U2A-SCL)") (class "Default")
      (node (ref "R28A") (pin "2") (pinfunction "2_2") (pintype "passive"))
      (node (ref "U2A") (pin "11") (pinfunction "SCL_11") (pintype "passive"))
    )
    (net (code "73") (name "Net-(U2A-SCLK)") (class "Default")
      (node (ref "R25A") (pin "2") (pinfunction "2_2") (pintype "passive"))
      (node (ref "U2A") (pin "7") (pinfunction "SCLK_7") (pintype "passive"))
    )
    (net (code "74") (name "Net-(U2A-SDA)") (class "Default")
      (node (ref "R27A") (pin "2") (pinfunction "2_2") (pintype "passive"))
      (node (ref "U2A") (pin "10") (pinfunction "SDA_10") (pintype "passive"))
    )
    (net (code "75") (name "Net-(U2A-SDIN)") (class "Default")
      (node (ref "R23A") (pin "2") (pinfunction "2_2") (pintype "passive"))
      (node (ref "U2A") (pin "8") (pinfunction "SDIN_8") (pintype "passive"))
    )
    (net (code "76") (name "Net-(U2A-SDOUT)") (class "Default")
      (node (ref "R21A") (pin "1") (pinfunction "1_1") (pintype "passive"))
      (node (ref "U2A") (pin "9") (pinfunction "SDOUT_9") (pintype "passive"))
    )
    (net (code "77") (name "Net-(U2A-VR_DIG)") (class "Default")
      (node (ref "C55A") (pin "2") (pinfunction "2_2") (pintype "passive"))
      (node (ref "U2A") (pin "4") (pinfunction "VR_DIG_4") (pintype "passive"))
    )
    (net (code "78") (name "unconnected-(MK_T1A-PadMK_B)") (class "Default")
      (node (ref "MK_T1A") (pin "MK_B") (pinfunction "MK_B_MK_B") (pintype "passive"))
    )
    (net (code "79") (name "unconnected-(MK_T1A-PadMK_T)") (class "Default")
      (node (ref "MK_T1A") (pin "MK_T") (pinfunction "MK_T_MK_T") (pintype "passive"))
    )
    (net (code "80") (name "unconnected-(MK_T2A-PadMK_B)") (class "Default")
      (node (ref "MK_T2A") (pin "MK_B") (pinfunction "MK_B_MK_B") (pintype "passive"))
    )
    (net (code "81") (name "unconnected-(MK_T2A-PadMK_T)") (class "Default")
      (node (ref "MK_T2A") (pin "MK_T") (pinfunction "MK_T_MK_T") (pintype "passive"))
    )
    (net (code "82") (name "unconnected-(U1A-GPIO2-Pad11)") (class "Default")
      (node (ref "U1A") (pin "11") (pinfunction "GPIO2_11") (pintype "passive+no_connect"))
    )
  )
)
